# PicoUSBMotherboardV3_0.net
KiCad netlist of a schematic drawn in EasyEDA Pro
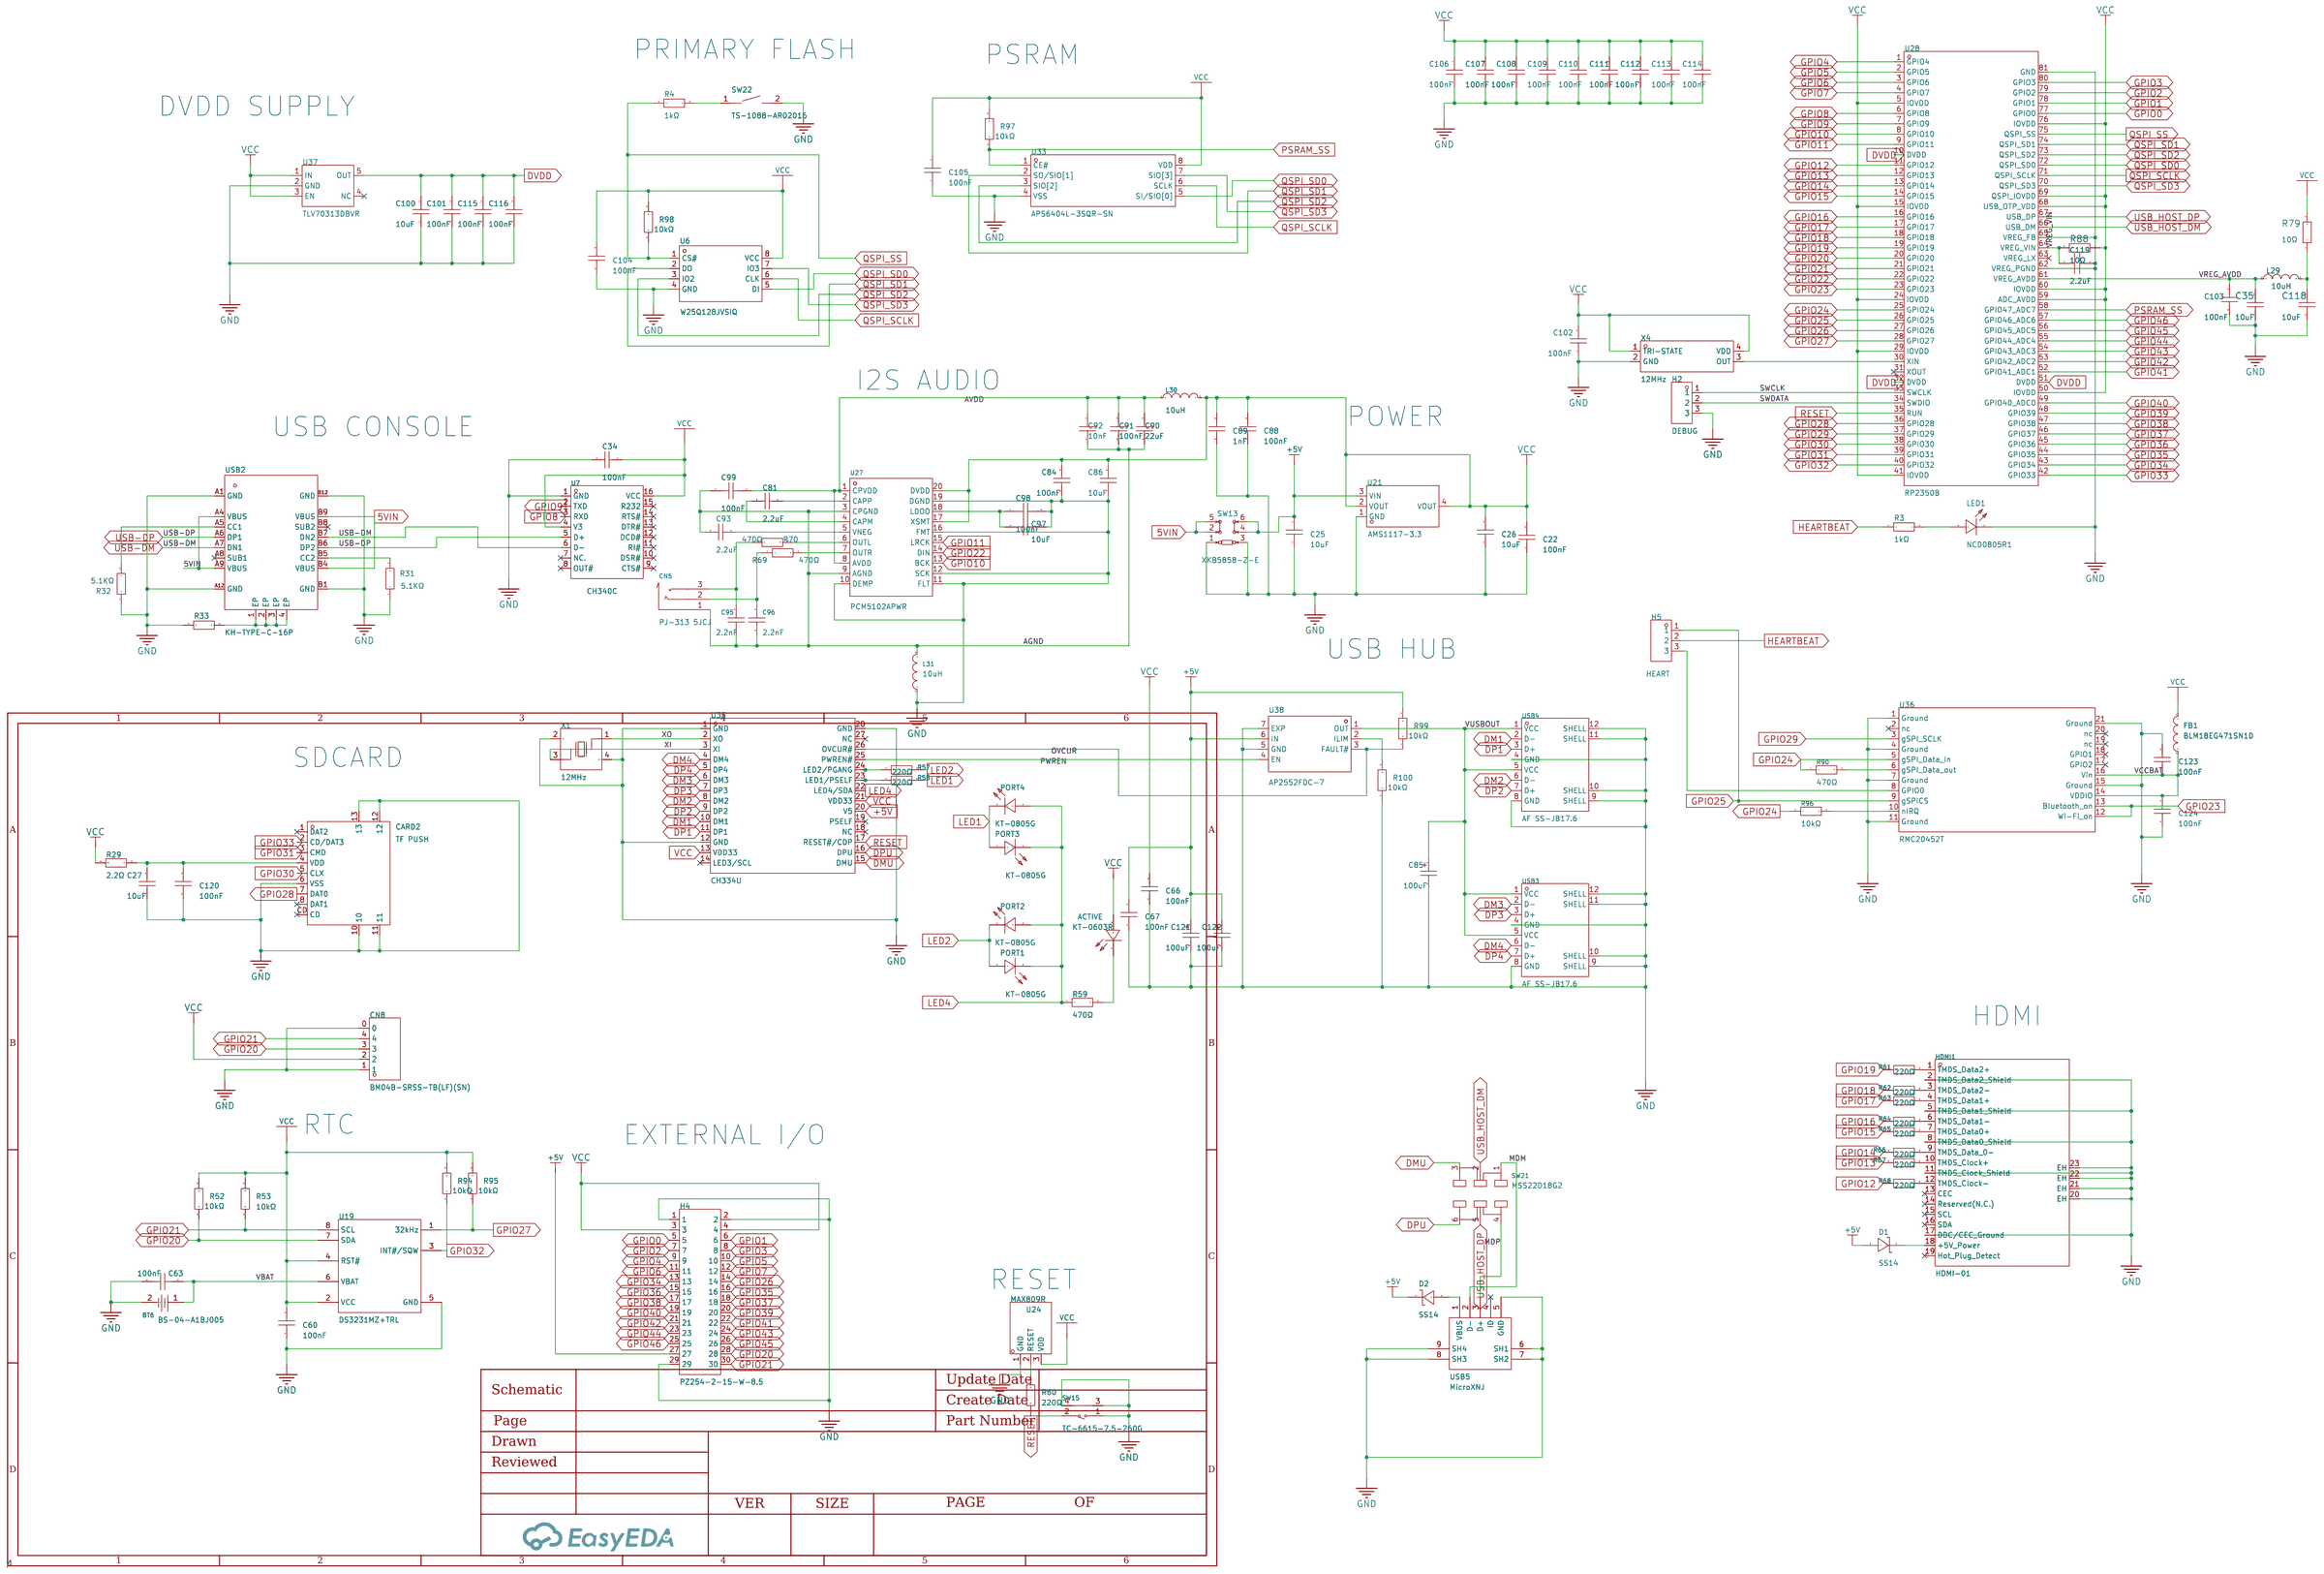
[diagram p0: schematic sheet]

(export (version "E")
  (design (tool "Eeschema 10.0.6"))
  (components
    (comp (ref "ACTIVE")
      (value "KT-0603R")
      (footprint "easyedapro:LED0603-RD")
      (fields (field (name "Manufacturer") "KENTO"))
      (libsource (lib "easyedapro") (part "KT-0603R"))
    )
    (comp (ref "BT6")
      (value "BS-04-A1BJ005")
      (footprint "easyedapro:BAT-TH_BS-04-A1BJ004")
      (fields (field (name "Manufacturer") "MYOUNG(美阳)"))
      (libsource (lib "easyedapro") (part "BS-04-A1BJ005"))
    )
    (comp (ref "C22")
      (value "100nF")
      (fields
        (field (name "Manufacturer Part") "CL05B104KO5NNNC")
        (field (name "Manufacturer") "SAMSUNG(三星)")
      )
      (libsource (lib "easyedapro") (part "cl10a225ko8nnnc"))
    )
    (comp (ref "C25")
      (value "10uF")
      (footprint "easyedapro:C1206")
      (fields
        (field (name "Manufacturer Part") "CL31A106KBHNNNE")
        (field (name "Manufacturer") "SAMSUNG(三星)")
      )
      (libsource (lib "easyedapro") (part "CL31A106KBHNNNE"))
    )
    (comp (ref "C26")
      (value "10uF")
      (footprint "easyedapro:C1206")
      (fields
        (field (name "Manufacturer Part") "CL31A106KBHNNNE")
        (field (name "Manufacturer") "SAMSUNG(三星)")
      )
      (libsource (lib "easyedapro") (part "CL31A106KBHNNNE"))
    )
    (comp (ref "C27")
      (value "10uF")
      (footprint "easyedapro:C1206")
      (fields
        (field (name "Manufacturer Part") "CL31A106KBHNNNE")
        (field (name "Manufacturer") "SAMSUNG(三星)")
      )
      (libsource (lib "easyedapro") (part "CL31A106KBHNNNE"))
    )
    (comp (ref "C34")
      (value "100nF")
      (fields
        (field (name "Manufacturer Part") "CL05B104KO5NNNC")
        (field (name "Manufacturer") "SAMSUNG(三星)")
      )
      (libsource (lib "easyedapro") (part "cl10a225ko8nnnc"))
    )
    (comp (ref "C35")
      (value "10uF")
      (footprint "easyedapro:C1206")
      (fields
        (field (name "Manufacturer Part") "CL31A106KBHNNNE")
        (field (name "Manufacturer") "SAMSUNG(三星)")
      )
      (libsource (lib "easyedapro") (part "CL31A106KBHNNNE"))
    )
    (comp (ref "C60")
      (value "100nF")
      (footprint "easyedapro:C0603")
      (fields
        (field (name "Manufacturer Part") "CL05B104KO5NNNC")
        (field (name "Manufacturer") "SAMSUNG(三星)")
      )
      (libsource (lib "easyedapro") (part "CL10A225KO8NNNC"))
    )
    (comp (ref "C63")
      (value "100nF")
      (footprint "easyedapro:C0402")
      (fields
        (field (name "Manufacturer Part") "CL05B104KB54PNC")
        (field (name "Manufacturer") "SAMSUNG(三星)")
      )
      (libsource (lib "easyedapro") (part "CL05B104KB54PNC"))
    )
    (comp (ref "C66")
      (value "100nF")
      (fields
        (field (name "Manufacturer Part") "CL05B104KO5NNNC")
        (field (name "Manufacturer") "SAMSUNG(三星)")
      )
      (libsource (lib "easyedapro") (part "cl10a225ko8nnnc"))
    )
    (comp (ref "C67")
      (value "100nF")
      (fields
        (field (name "Manufacturer Part") "CL05B104KO5NNNC")
        (field (name "Manufacturer") "SAMSUNG(三星)")
      )
      (libsource (lib "easyedapro") (part "cl10a225ko8nnnc"))
    )
    (comp (ref "C81")
      (value "2.2uF")
      (footprint "easyedapro:C0603")
      (fields
        (field (name "Manufacturer Part") "CL10A225KO8NNNC")
        (field (name "Manufacturer") "SAMSUNG(三星)")
      )
      (libsource (lib "easyedapro") (part "CL10A225KO8NNNC"))
    )
    (comp (ref "C84")
      (value "100nF")
      (fields
        (field (name "Manufacturer Part") "CL05B104KO5NNNC")
        (field (name "Manufacturer") "SAMSUNG(三星)")
      )
      (libsource (lib "easyedapro") (part "cl10a225ko8nnnc"))
    )
    (comp (ref "C85")
      (value "100uF")
      (footprint "easyedapro:CASE-B_3528")
      (fields (field (name "Manufacturer Part") "TAJB107K006RNJ") (field (name "Manufacturer") "Kyocera AVX"))
      (libsource (lib "easyedapro") (part "TAJB107K006RNJ"))
    )
    (comp (ref "C86")
      (value "10uF")
      (footprint "easyedapro:C1206")
      (fields
        (field (name "Manufacturer Part") "CL31A106KBHNNNE")
        (field (name "Manufacturer") "SAMSUNG(三星)")
      )
      (libsource (lib "easyedapro") (part "CL31A106KBHNNNE"))
    )
    (comp (ref "C88")
      (value "100nF")
      (fields
        (field (name "Manufacturer Part") "CL05B104KO5NNNC")
        (field (name "Manufacturer") "SAMSUNG(三星)")
      )
      (libsource (lib "easyedapro") (part "cl10a225ko8nnnc"))
    )
    (comp (ref "C89")
      (value "1nF")
      (footprint "easyedapro:C0805")
      (fields
        (field (name "Manufacturer Part") "CL21B102KBCNNNC")
        (field (name "Manufacturer") "SAMSUNG(三星)")
      )
      (libsource (lib "easyedapro") (part "CL21B102KBCNNNC"))
    )
    (comp (ref "C90")
      (value "22uF")
      (footprint "easyedapro:C1206")
      (fields
        (field (name "Manufacturer Part") "CL31A226KAHNNNE")
        (field (name "Manufacturer") "SAMSUNG(三星)")
      )
      (libsource (lib "easyedapro") (part "CL31A226KAHNNNE"))
    )
    (comp (ref "C91")
      (value "100nF")
      (fields
        (field (name "Manufacturer Part") "CL05B104KO5NNNC")
        (field (name "Manufacturer") "SAMSUNG(三星)")
      )
      (libsource (lib "easyedapro") (part "cl10a225ko8nnnc"))
    )
    (comp (ref "C92")
      (value "10nF")
      (footprint "easyedapro:C0805")
      (fields
        (field (name "Manufacturer Part") "CL21B103KBANNNC")
        (field (name "Manufacturer") "SAMSUNG(三星)")
      )
      (libsource (lib "easyedapro") (part "CL21B103KBANNNC"))
    )
    (comp (ref "C93")
      (value "2.2uF")
      (footprint "easyedapro:C0603")
      (fields
        (field (name "Manufacturer Part") "CL10A225KO8NNNC")
        (field (name "Manufacturer") "SAMSUNG(三星)")
      )
      (libsource (lib "easyedapro") (part "CL10A225KO8NNNC"))
    )
    (comp (ref "C95")
      (value "2.2nF")
      (footprint "easyedapro:C0805")
      (fields
        (field (name "Manufacturer Part") "CL21C222JBFNNNE")
        (field (name "Manufacturer") "SAMSUNG(三星)")
      )
      (libsource (lib "easyedapro") (part "CL21C222JBFNNNE"))
    )
    (comp (ref "C96")
      (value "2.2nF")
      (footprint "easyedapro:C0805")
      (fields
        (field (name "Manufacturer Part") "CL21C222JBFNNNE")
        (field (name "Manufacturer") "SAMSUNG(三星)")
      )
      (libsource (lib "easyedapro") (part "CL21C222JBFNNNE"))
    )
    (comp (ref "C97")
      (value "10uF")
      (footprint "easyedapro:C0805")
      (fields
        (field (name "Manufacturer Part") "CL21A106KAYNNNE")
        (field (name "Manufacturer") "SAMSUNG(三星)")
      )
      (libsource (lib "easyedapro") (part "CL21A106KAYNNNE"))
    )
    (comp (ref "C98")
      (value "100nF")
      (footprint "easyedapro:C0805")
      (fields
        (field (name "Manufacturer Part") "CC0805KRX7R9BB104")
        (field (name "Manufacturer") "YAGEO(国巨)")
      )
      (libsource (lib "easyedapro") (part "CC0805KRX7R9BB104"))
    )
    (comp (ref "C99")
      (value "100nF")
      (footprint "easyedapro:C0805")
      (fields
        (field (name "Manufacturer Part") "CC0805KRX7R9BB104")
        (field (name "Manufacturer") "YAGEO(国巨)")
      )
      (libsource (lib "easyedapro") (part "CC0805KRX7R9BB104"))
    )
    (comp (ref "C100")
      (value "10uF")
      (footprint "easyedapro:C1206")
      (fields
        (field (name "Manufacturer Part") "CL31A106KBHNNNE")
        (field (name "Manufacturer") "SAMSUNG(三星)")
      )
      (libsource (lib "easyedapro") (part "CL31A106KBHNNNE"))
    )
    (comp (ref "C101")
      (value "100nF")
      (fields
        (field (name "Manufacturer Part") "CL05B104KO5NNNC")
        (field (name "Manufacturer") "SAMSUNG(三星)")
      )
      (libsource (lib "easyedapro") (part "cl10a225ko8nnnc"))
    )
    (comp (ref "C102")
      (value "100nF")
      (fields
        (field (name "Manufacturer Part") "CL05B104KO5NNNC")
        (field (name "Manufacturer") "SAMSUNG(三星)")
      )
      (libsource (lib "easyedapro") (part "cl10a225ko8nnnc"))
    )
    (comp (ref "C103")
      (value "100nF")
      (fields
        (field (name "Manufacturer Part") "CL05B104KO5NNNC")
        (field (name "Manufacturer") "SAMSUNG(三星)")
      )
      (libsource (lib "easyedapro") (part "cl10a225ko8nnnc"))
    )
    (comp (ref "C104")
      (value "100nF")
      (footprint "easyedapro:C0805")
      (fields
        (field (name "Manufacturer Part") "CL21B104KCFNNNE")
        (field (name "Manufacturer") "SAMSUNG(三星)")
      )
      (libsource (lib "easyedapro") (part "CL21B104KCFNNNE"))
    )
    (comp (ref "C105")
      (value "100nF")
      (fields
        (field (name "Manufacturer Part") "CL05B104KO5NNNC")
        (field (name "Manufacturer") "SAMSUNG(三星)")
      )
      (libsource (lib "easyedapro") (part "cl10a225ko8nnnc"))
    )
    (comp (ref "C106")
      (value "100nF")
      (fields
        (field (name "Manufacturer Part") "CL05B104KO5NNNC")
        (field (name "Manufacturer") "SAMSUNG(三星)")
      )
      (libsource (lib "easyedapro") (part "cl10a225ko8nnnc"))
    )
    (comp (ref "C107")
      (value "100nF")
      (fields
        (field (name "Manufacturer Part") "CL05B104KO5NNNC")
        (field (name "Manufacturer") "SAMSUNG(三星)")
      )
      (libsource (lib "easyedapro") (part "cl10a225ko8nnnc"))
    )
    (comp (ref "C108")
      (value "100nF")
      (fields
        (field (name "Manufacturer Part") "CL05B104KO5NNNC")
        (field (name "Manufacturer") "SAMSUNG(三星)")
      )
      (libsource (lib "easyedapro") (part "cl10a225ko8nnnc"))
    )
    (comp (ref "C109")
      (value "100nF")
      (fields
        (field (name "Manufacturer Part") "CL05B104KO5NNNC")
        (field (name "Manufacturer") "SAMSUNG(三星)")
      )
      (libsource (lib "easyedapro") (part "cl10a225ko8nnnc"))
    )
    (comp (ref "C110")
      (value "100nF")
      (fields
        (field (name "Manufacturer Part") "CL05B104KO5NNNC")
        (field (name "Manufacturer") "SAMSUNG(三星)")
      )
      (libsource (lib "easyedapro") (part "cl10a225ko8nnnc"))
    )
    (comp (ref "C111")
      (value "100nF")
      (fields
        (field (name "Manufacturer Part") "CL05B104KO5NNNC")
        (field (name "Manufacturer") "SAMSUNG(三星)")
      )
      (libsource (lib "easyedapro") (part "cl10a225ko8nnnc"))
    )
    (comp (ref "C112")
      (value "100nF")
      (fields
        (field (name "Manufacturer Part") "CL05B104KO5NNNC")
        (field (name "Manufacturer") "SAMSUNG(三星)")
      )
      (libsource (lib "easyedapro") (part "cl10a225ko8nnnc"))
    )
    (comp (ref "C113")
      (value "100nF")
      (fields
        (field (name "Manufacturer Part") "CL05B104KO5NNNC")
        (field (name "Manufacturer") "SAMSUNG(三星)")
      )
      (libsource (lib "easyedapro") (part "cl10a225ko8nnnc"))
    )
    (comp (ref "C114")
      (value "100nF")
      (fields
        (field (name "Manufacturer Part") "CL05B104KO5NNNC")
        (field (name "Manufacturer") "SAMSUNG(三星)")
      )
      (libsource (lib "easyedapro") (part "cl10a225ko8nnnc"))
    )
    (comp (ref "C115")
      (value "100nF")
      (fields
        (field (name "Manufacturer Part") "CL05B104KO5NNNC")
        (field (name "Manufacturer") "SAMSUNG(三星)")
      )
      (libsource (lib "easyedapro") (part "cl10a225ko8nnnc"))
    )
    (comp (ref "C116")
      (value "100nF")
      (fields
        (field (name "Manufacturer Part") "CL05B104KO5NNNC")
        (field (name "Manufacturer") "SAMSUNG(三星)")
      )
      (libsource (lib "easyedapro") (part "cl10a225ko8nnnc"))
    )
    (comp (ref "C118")
      (value "10uF")
      (footprint "easyedapro:C1206")
      (fields
        (field (name "Manufacturer Part") "CL31A106KBHNNNE")
        (field (name "Manufacturer") "SAMSUNG(三星)")
      )
      (libsource (lib "easyedapro") (part "CL31A106KBHNNNE"))
    )
    (comp (ref "C119")
      (value "2.2uF")
      (footprint "easyedapro:C0402")
      (fields
        (field (name "Manufacturer Part") "CL05A225MQ5NSNC")
        (field (name "Manufacturer") "SAMSUNG(三星)")
      )
      (libsource (lib "easyedapro") (part "CL05A225MQ5NSNC"))
    )
    (comp (ref "C120")
      (value "100nF")
      (footprint "easyedapro:C0805")
      (fields
        (field (name "Manufacturer Part") "CL21B104KCFNNNE")
        (field (name "Manufacturer") "SAMSUNG(三星)")
      )
      (libsource (lib "easyedapro") (part "CL21B104KCFNNNE"))
    )
    (comp (ref "C121")
      (value "100uF")
      (footprint "easyedapro:CASE-B_3528")
      (fields (field (name "Manufacturer Part") "TAJB107K006RNJ") (field (name "Manufacturer") "Kyocera AVX"))
      (libsource (lib "easyedapro") (part "TAJB107K006RNJ"))
    )
    (comp (ref "C122")
      (value "100uF")
      (footprint "easyedapro:CASE-B_3528")
      (fields (field (name "Manufacturer Part") "TAJB107K006RNJ") (field (name "Manufacturer") "Kyocera AVX"))
      (libsource (lib "easyedapro") (part "TAJB107K006RNJ"))
    )
    (comp (ref "C123")
      (value "100nF")
      (fields
        (field (name "Manufacturer Part") "CL05B104KO5NNNC")
        (field (name "Manufacturer") "SAMSUNG(三星)")
      )
      (libsource (lib "easyedapro") (part "cl10a225ko8nnnc"))
    )
    (comp (ref "C124")
      (value "100nF")
      (fields
        (field (name "Manufacturer Part") "CL05B104KO5NNNC")
        (field (name "Manufacturer") "SAMSUNG(三星)")
      )
      (libsource (lib "easyedapro") (part "cl10a225ko8nnnc"))
    )
    (comp (ref "CARD2")
      (value "TF PUSH")
      (footprint "easyedapro:TF-SMD_TF-PUSH")
      (fields (field (name "Manufacturer") "SHOU HAN(首韩)"))
      (libsource (lib "easyedapro") (part "TF PUSH"))
    )
    (comp (ref "CN5")
      (value "PJ-313 5JCJ")
      (footprint "easyedapro:AUDIO-TH_PJ-313_5JCJ")
      (fields (field (name "Manufacturer") "SHOU HAN(首韩)"))
      (libsource (lib "easyedapro") (part "PJ-313 5JCJ"))
    )
    (comp (ref "CN8")
      (value "BM04B-SRSS-TB(LF)(SN)")
      (footprint "easyedapro:CONN-SMD_BM04B-SRSS-TB")
      (fields (field (name "Manufacturer") "JST"))
      (libsource (lib "easyedapro") (part "BM04B-SRSS-TB(LF)(SN)"))
    )
    (comp (ref "D1")
      (value "SS14")
      (footprint "easyedapro:SMA_L4.2-W2.6-LS5.3-RD")
      (fields (field (name "Manufacturer") "MDD(辰达半导体)"))
      (libsource (lib "easyedapro") (part "SS14"))
    )
    (comp (ref "D2")
      (value "SS14")
      (footprint "easyedapro:SMA_L4.2-W2.6-LS5.3-RD")
      (fields (field (name "Manufacturer") "MDD(辰达半导体)"))
      (libsource (lib "easyedapro") (part "SS14"))
    )
    (comp (ref "FB1")
      (value "BLM18EG471SN1D")
      (footprint "easyedapro:L0603")
      (fields (field (name "Manufacturer") "muRata(村田)"))
      (libsource (lib "easyedapro") (part "BLM18EG471SN1D"))
    )
    (comp (ref "H2")
      (value "DEBUG")
      (footprint "easyedapro:HDR-TH_3P-P2.54-V-M")
      (fields (field (name "Manufacturer Part") "PZ254V-11-03P") (field (name "Manufacturer") "XFCN(兴飞)"))
      (libsource (lib "easyedapro") (part "PZ254V-11-03P_C2937625"))
    )
    (comp (ref "H4")
      (value "PZ254-2-15-W-8.5")
      (footprint "easyedapro:HDR-TH_30P-P2.54-H-M-R2-C15-S2.54-N")
      (fields (field (name "Manufacturer") "HCTL(华灿天禄)"))
      (libsource (lib "easyedapro") (part "PZ254-2-15-W-8.5"))
    )
    (comp (ref "H5")
      (value "HEART")
      (footprint "easyedapro:HDR-TH_3P-P2.54-V-M")
      (fields (field (name "Manufacturer Part") "PZ254V-11-03P") (field (name "Manufacturer") "XFCN(兴飞)"))
      (libsource (lib "easyedapro") (part "PZ254V-11-03P_C2937625"))
    )
    (comp (ref "HDMI1")
      (value "HDMI-01")
      (footprint "easyedapro:USB-SMD_HDMI-01")
      (fields (field (name "Manufacturer") "HCTL(华灿天禄)"))
      (libsource (lib "easyedapro") (part "HDMI-01"))
    )
    (comp (ref "L29")
      (value "10uH")
      (fields
        (field (name "Manufacturer Part") "SDFL2012S100KTF")
        (field (name "Manufacturer") "Sunlord(顺络)")
      )
      (libsource (lib "easyedapro") (part "SDFL2012S100KTF"))
    )
    (comp (ref "L30")
      (value "10uH")
      (footprint "easyedapro:L0805")
      (fields (field (name "Manufacturer Part") "MLZ2012M100HT000") (field (name "Manufacturer") "TDK"))
      (libsource (lib "easyedapro") (part "MLZ2012M100HT000"))
    )
    (comp (ref "L31")
      (value "10uH")
      (footprint "easyedapro:L0805")
      (fields (field (name "Manufacturer Part") "MLZ2012M100HT000") (field (name "Manufacturer") "TDK"))
      (libsource (lib "easyedapro") (part "MLZ2012M100HT000"))
    )
    (comp (ref "LED1")
      (value "NCD0805R1")
      (footprint "easyedapro:LED0805-RD")
      (description "Emitted Color:红灯")
      (fields (field (name "Manufacturer") "国星光电"))
      (libsource (lib "easyedapro") (part "FC-2012HRK-620D"))
    )
    (comp (ref "PORT1")
      (value "KT-0805G")
      (footprint "easyedapro:LED0805-R-RD")
      (fields (field (name "Manufacturer") "KENTO"))
      (libsource (lib "easyedapro") (part "0805G (Green)"))
    )
    (comp (ref "PORT2")
      (value "KT-0805G")
      (footprint "easyedapro:LED0805-R-RD")
      (fields (field (name "Manufacturer") "KENTO"))
      (libsource (lib "easyedapro") (part "0805G (Green)"))
    )
    (comp (ref "PORT3")
      (value "KT-0805G")
      (footprint "easyedapro:LED0805-R-RD")
      (fields (field (name "Manufacturer") "KENTO"))
      (libsource (lib "easyedapro") (part "0805G (Green)"))
    )
    (comp (ref "PORT4")
      (value "KT-0805G")
      (footprint "easyedapro:LED0805-R-RD")
      (fields (field (name "Manufacturer") "KENTO"))
      (libsource (lib "easyedapro") (part "0805G (Green)"))
    )
    (comp (ref "R3")
      (value "1kΩ")
      (footprint "easyedapro:R0603")
      (fields
        (field (name "Manufacturer Part") "0603WAF1001T5E")
        (field (name "Manufacturer") "UNI-ROYAL(厚声)")
      )
      (libsource (lib "easyedapro") (part "0603WAF1001T5E"))
    )
    (comp (ref "R4")
      (value "1kΩ")
      (footprint "easyedapro:R0603")
      (fields
        (field (name "Manufacturer Part") "0603WAF1001T5E")
        (field (name "Manufacturer") "UNI-ROYAL(厚声)")
      )
      (libsource (lib "easyedapro") (part "0603WAF1001T5E"))
    )
    (comp (ref "R29")
      (value "2.2Ω")
      (footprint "easyedapro:R0805")
      (fields (field (name "Manufacturer") "UNI-ROYAL(厚声)"))
      (libsource (lib "easyedapro") (part "0805W8F220KT5E"))
    )
    (comp (ref "R31")
      (value "5.1kΩ")
      (fields
        (field (name "Manufacturer Part") "5.1KΩ")
        (field (name "Manufacturer") "UNI-ROYAL(厚声)")
        (field (name "Tolerance") "±1%")
      )
      (libsource (lib "easyedapro") (part "0603waf5101t5e"))
    )
    (comp (ref "R32")
      (value "5.1kΩ")
      (fields
        (field (name "Manufacturer Part") "5.1KΩ")
        (field (name "Manufacturer") "UNI-ROYAL(厚声)")
        (field (name "Tolerance") "±1%")
      )
      (libsource (lib "easyedapro") (part "0603waf5101t5e"))
    )
    (comp (ref "R33")
      (value "1MΩ")
      (fields
        (field (name "Manufacturer Part") "0402WGF1004TCE")
        (field (name "Manufacturer") "UNI-ROYAL(厚声)")
      )
      (libsource (lib "easyedapro") (part "0603waf1004t5e"))
    )
    (comp (ref "R52")
      (value "10kΩ")
      (footprint "easyedapro:R0805")
      (fields
        (field (name "Manufacturer Part") "0805W8F1002T5E")
        (field (name "Manufacturer") "UNI-ROYAL(厚声)")
      )
      (libsource (lib "easyedapro") (part "0805W8F1002T5E"))
    )
    (comp (ref "R53")
      (value "10kΩ")
      (footprint "easyedapro:R0805")
      (fields
        (field (name "Manufacturer Part") "0805W8F1002T5E")
        (field (name "Manufacturer") "UNI-ROYAL(厚声)")
      )
      (libsource (lib "easyedapro") (part "0805W8F1002T5E"))
    )
    (comp (ref "R57")
      (value "220Ω")
      (footprint "easyedapro:R0805")
      (fields
        (field (name "Manufacturer Part") "0805W8F2200T5E")
        (field (name "Manufacturer") "UNI-ROYAL(厚声)")
      )
      (libsource (lib "easyedapro") (part "0805W8F2200T5E"))
    )
    (comp (ref "R58")
      (value "220Ω")
      (footprint "easyedapro:R0805")
      (fields
        (field (name "Manufacturer Part") "0805W8F2200T5E")
        (field (name "Manufacturer") "UNI-ROYAL(厚声)")
      )
      (libsource (lib "easyedapro") (part "0805W8F2200T5E"))
    )
    (comp (ref "R59")
      (value "470Ω")
      (footprint "easyedapro:R0603")
      (fields
        (field (name "Manufacturer Part") "0603WAF4700T5E")
        (field (name "Manufacturer") "UNI-ROYAL(厚声)")
      )
      (libsource (lib "easyedapro") (part "0603WAF4700T5E"))
    )
    (comp (ref "R60")
      (value "220Ω")
      (footprint "easyedapro:R0603")
      (fields
        (field (name "Manufacturer Part") "0603WAF2200T5E")
        (field (name "Manufacturer") "UNI-ROYAL(厚声)")
      )
      (libsource (lib "easyedapro") (part "0603WAF2200T5E"))
    )
    (comp (ref "R61")
      (value "220Ω")
      (footprint "easyedapro:R0603")
      (fields
        (field (name "Manufacturer Part") "0603WAF2200T5E")
        (field (name "Manufacturer") "UNI-ROYAL(厚声)")
      )
      (libsource (lib "easyedapro") (part "0603WAF2200T5E"))
    )
    (comp (ref "R62")
      (value "220Ω")
      (footprint "easyedapro:R0603")
      (fields
        (field (name "Manufacturer Part") "0603WAF2200T5E")
        (field (name "Manufacturer") "UNI-ROYAL(厚声)")
      )
      (libsource (lib "easyedapro") (part "0603WAF2200T5E"))
    )
    (comp (ref "R63")
      (value "220Ω")
      (footprint "easyedapro:R0603")
      (fields
        (field (name "Manufacturer Part") "0603WAF2200T5E")
        (field (name "Manufacturer") "UNI-ROYAL(厚声)")
      )
      (libsource (lib "easyedapro") (part "0603WAF2200T5E"))
    )
    (comp (ref "R64")
      (value "220Ω")
      (footprint "easyedapro:R0603")
      (fields
        (field (name "Manufacturer Part") "0603WAF2200T5E")
        (field (name "Manufacturer") "UNI-ROYAL(厚声)")
      )
      (libsource (lib "easyedapro") (part "0603WAF2200T5E"))
    )
    (comp (ref "R65")
      (value "220Ω")
      (footprint "easyedapro:R0603")
      (fields
        (field (name "Manufacturer Part") "0603WAF2200T5E")
        (field (name "Manufacturer") "UNI-ROYAL(厚声)")
      )
      (libsource (lib "easyedapro") (part "0603WAF2200T5E"))
    )
    (comp (ref "R66")
      (value "220Ω")
      (footprint "easyedapro:R0603")
      (fields
        (field (name "Manufacturer Part") "0603WAF2200T5E")
        (field (name "Manufacturer") "UNI-ROYAL(厚声)")
      )
      (libsource (lib "easyedapro") (part "0603WAF2200T5E"))
    )
    (comp (ref "R67")
      (value "220Ω")
      (footprint "easyedapro:R0603")
      (fields
        (field (name "Manufacturer Part") "0603WAF2200T5E")
        (field (name "Manufacturer") "UNI-ROYAL(厚声)")
      )
      (libsource (lib "easyedapro") (part "0603WAF2200T5E"))
    )
    (comp (ref "R68")
      (value "220Ω")
      (footprint "easyedapro:R0603")
      (fields
        (field (name "Manufacturer Part") "0603WAF2200T5E")
        (field (name "Manufacturer") "UNI-ROYAL(厚声)")
      )
      (libsource (lib "easyedapro") (part "0603WAF2200T5E"))
    )
    (comp (ref "R69")
      (value "470Ω")
      (footprint "easyedapro:R0603")
      (fields
        (field (name "Manufacturer Part") "0603WAF4700T5E")
        (field (name "Manufacturer") "UNI-ROYAL(厚声)")
      )
      (libsource (lib "easyedapro") (part "0603WAF4700T5E"))
    )
    (comp (ref "R70")
      (value "470Ω")
      (footprint "easyedapro:R0603")
      (fields
        (field (name "Manufacturer Part") "0603WAF4700T5E")
        (field (name "Manufacturer") "UNI-ROYAL(厚声)")
      )
      (libsource (lib "easyedapro") (part "0603WAF4700T5E"))
    )
    (comp (ref "R79")
      (value "10Ω")
      (footprint "easyedapro:R0805_NEW")
      (fields
        (field (name "Manufacturer Part") "0805W8F100JT5E")
        (field (name "Manufacturer") "UNI-ROYAL(厚声)")
      )
      (libsource (lib "easyedapro") (part "0805W8F100JT5E"))
    )
    (comp (ref "R88")
      (value "10Ω")
      (footprint "easyedapro:R0805_NEW")
      (fields
        (field (name "Manufacturer Part") "0805W8F100JT5E")
        (field (name "Manufacturer") "UNI-ROYAL(厚声)")
      )
      (libsource (lib "easyedapro") (part "0805W8F100JT5E"))
    )
    (comp (ref "R90")
      (value "470Ω")
      (footprint "easyedapro:R0402")
      (fields
        (field (name "Manufacturer Part") "0402WGF4700TCE")
        (field (name "Manufacturer") "UNI-ROYAL(厚声)")
      )
      (libsource (lib "easyedapro") (part "0402WGF4700TCE"))
    )
    (comp (ref "R94")
      (value "10kΩ")
      (footprint "easyedapro:R0805")
      (fields
        (field (name "Manufacturer Part") "0805W8F1002T5E")
        (field (name "Manufacturer") "UNI-ROYAL(厚声)")
      )
      (libsource (lib "easyedapro") (part "0805W8F1002T5E"))
    )
    (comp (ref "R95")
      (value "10kΩ")
      (footprint "easyedapro:R0805")
      (fields
        (field (name "Manufacturer Part") "0805W8F1002T5E")
        (field (name "Manufacturer") "UNI-ROYAL(厚声)")
      )
      (libsource (lib "easyedapro") (part "0805W8F1002T5E"))
    )
    (comp (ref "R96")
      (value "10kΩ")
      (footprint "easyedapro:R0603")
      (fields
        (field (name "Manufacturer Part") "0603WAF1002T5E")
        (field (name "Manufacturer") "UNI-ROYAL(厚声)")
      )
      (libsource (lib "easyedapro") (part "0603WAF1002T5E"))
    )
    (comp (ref "R97")
      (value "10kΩ")
      (footprint "easyedapro:R0805")
      (fields
        (field (name "Manufacturer Part") "0805W8F1002T5E")
        (field (name "Manufacturer") "UNI-ROYAL(厚声)")
      )
      (libsource (lib "easyedapro") (part "0805W8F1002T5E"))
    )
    (comp (ref "R98")
      (value "10kΩ")
      (footprint "easyedapro:R0805")
      (fields
        (field (name "Manufacturer Part") "0805W8F1002T5E")
        (field (name "Manufacturer") "UNI-ROYAL(厚声)")
      )
      (libsource (lib "easyedapro") (part "0805W8F1002T5E"))
    )
    (comp (ref "R99")
      (value "10kΩ")
      (footprint "easyedapro:R0805")
      (fields
        (field (name "Manufacturer Part") "0805W8F1002T5E")
        (field (name "Manufacturer") "UNI-ROYAL(厚声)")
      )
      (libsource (lib "easyedapro") (part "0805W8F1002T5E"))
    )
    (comp (ref "R100")
      (value "10kΩ")
      (footprint "easyedapro:R0805")
      (fields
        (field (name "Manufacturer Part") "0805W8F1002T5E")
        (field (name "Manufacturer") "UNI-ROYAL(厚声)")
      )
      (libsource (lib "easyedapro") (part "0805W8F1002T5E"))
    )
    (comp (ref "SW13")
      (value "XKB5858-Z-E")
      (footprint "easyedapro:SW-TH_XKB5858-Z-E")
      (fields (field (name "Manufacturer") "XKB Connectivity(中国星坤)"))
      (libsource (lib "easyedapro") (part "XKB5858-Z-E"))
    )
    (comp (ref "SW15")
      (value "TC-6615-7.5-260G")
      (footprint "easyedapro:SW-TH_4P-L7.5-W7.5-P4.50")
      (fields (field (name "Manufacturer") "HCTL(华灿天禄)"))
      (libsource (lib "easyedapro") (part "TC-6615-7.5-260G"))
    )
    (comp (ref "SW21")
      (value "MSS22D18G2")
      (footprint "easyedapro:SW-TH_MSS22D18GX")
      (fields (field (name "Manufacturer") "SHOU HAN(首韩)"))
      (libsource (lib "easyedapro") (part "MSS22D18G2"))
    )
    (comp (ref "SW22")
      (value "TS-1088-AR02016")
      (footprint "easyedapro:SW-SMD_L3.9-W3.0-P4.45")
      (fields (field (name "Manufacturer") "XUNPU(讯普)"))
      (libsource (lib "easyedapro") (part "TS-1088-AR02016"))
    )
    (comp (ref "U6")
      (value "W25Q128JVSIQ")
      (footprint "easyedapro:SOIC-8_L5.3-W5.3-P1.27-LS8.0-BL")
      (fields (field (name "Manufacturer") "WINBOND(华邦)"))
      (libsource (lib "easyedapro") (part "W25Q128JVSIQTR"))
    )
    (comp (ref "U7")
      (value "CH340C")
      (footprint "easyedapro:SOP-16_L10.0-W3.9-P1.27-LS6.0-BL")
      (fields (field (name "Manufacturer") "WCH(南京沁恒)"))
      (libsource (lib "easyedapro") (part "CH340C"))
    )
    (comp (ref "U19")
      (value "DS3231MZ+TRL")
      (footprint "easyedapro:SOIC-8_L4.9-W3.9-P1.27-LS6.0-BL")
      (fields (field (name "Manufacturer") "ADI(亚德诺)/MAXIM(美信)"))
      (libsource (lib "easyedapro") (part "DS3231MZ+"))
    )
    (comp (ref "U21")
      (value "AMS1117-3.3")
      (footprint "easyedapro:SOT-223-3_L6.5-W3.4-P2.30-LS7.0-BR")
      (fields (field (name "Manufacturer") "AMS"))
      (libsource (lib "easyedapro") (part "AMS1117-3.3"))
    )
    (comp (ref "U24")
      (value "MAX809R")
      (footprint "easyedapro:SOT-23-3_L2.9-W1.3-P1.90-LS2.4-BR")
      (fields (field (name "Manufacturer") "UMW(友台半导体)"))
      (libsource (lib "easyedapro") (part "MAX809R"))
    )
    (comp (ref "U27")
      (value "PCM5102APWR")
      (footprint "easyedapro:TSSOP-20_L6.5-W4.4-P0.65-LS6.4-BL")
      (fields (field (name "Manufacturer") "TI(德州仪器)"))
      (libsource (lib "easyedapro") (part "PCM5102APWR"))
    )
    (comp (ref "U28")
      (value "RP2350B")
      (footprint "easyedapro:QFN-80_L10.0-W10.0-P0.40-TL-EP3.4")
      (fields (field (name "Manufacturer") "Raspberry Pi(树莓派)"))
      (libsource (lib "easyedapro") (part "RP2350B_C42415655"))
    )
    (comp (ref "U33")
      (value "APS6404L-3SQR-SN")
      (footprint "easyedapro:SOIC-8_L4.9-W3.9-P1.27-LS6.0-BL")
      (fields (field (name "Manufacturer") "Apmemory"))
      (libsource (lib "easyedapro") (part "APS6404L-3SQR-SN_C5333729"))
    )
    (comp (ref "U35")
      (value "CH334U")
      (footprint "easyedapro:QSOP-28_L9.9-W3.9-P0.64-LS6.0-BL")
      (fields (field (name "Manufacturer") "WCH(南京沁恒)"))
      (libsource (lib "easyedapro") (part "CH334U"))
    )
    (comp (ref "U36")
      (value "RMC20452T")
      (footprint "easyedapro:WIRELM-SMD_RMC20452T")
      (fields (field (name "Manufacturer") "Raspberry Pi(树莓派)"))
      (libsource (lib "easyedapro") (part "RMC20452T_C49451547"))
    )
    (comp (ref "U37")
      (value "TLV70313DBVR")
      (footprint "easyedapro:SOT-23-5_L3.0-W1.5-P0.95-LS2.8-BL")
      (fields (field (name "Manufacturer") "TI(德州仪器)"))
      (libsource (lib "easyedapro") (part "TLV70313DBVR"))
    )
    (comp (ref "U38")
      (value "AP2552FDC-7")
      (footprint "easyedapro:WDFN-6_L2.0-W2.0-P0.65-BL-EP-1")
      (fields (field (name "Manufacturer") "DIODES(美台)"))
      (libsource (lib "easyedapro") (part "AP2552FDC-7"))
    )
    (comp (ref "USB2")
      (value "KH-TYPE-C-16P")
      (footprint "easyedapro:USB-C-SMD_KH-TYPE-C-16P")
      (fields (field (name "Manufacturer") "kinghelm(金航标)"))
      (libsource (lib "easyedapro") (part "KH-TYPE-C-16P"))
    )
    (comp (ref "USB3")
      (value "AF SS-JB17.6")
      (footprint "easyedapro:USB-A-TH_AF-SS-JB17.6")
      (fields (field (name "Manufacturer") "SHOU HAN(首韩)"))
      (libsource (lib "easyedapro") (part "AF SS-JB17.6"))
    )
    (comp (ref "USB4")
      (value "AF SS-JB17.6")
      (footprint "easyedapro:USB-A-TH_AF-SS-JB17.6")
      (fields (field (name "Manufacturer") "SHOU HAN(首韩)"))
      (libsource (lib "easyedapro") (part "AF SS-JB17.6"))
    )
    (comp (ref "USB5")
      (value "MicroXNJ")
      (footprint "easyedapro:MICRO-USB-SMD_MICROXNJ")
      (fields (field (name "Manufacturer") "SHOU HAN(首韩)"))
      (libsource (lib "easyedapro") (part "MICROXNJ"))
    )
    (comp (ref "X1")
      (value "12MHz")
      (footprint "easyedapro:OSC-SMD_4P-L3.2-W2.5-BL")
      (fields (field (name "Manufacturer Part") "X322512MSB4SI") (field (name "Manufacturer") "YXC(扬兴晶振)"))
      (libsource (lib "easyedapro") (part "X322512MSB4SI"))
    )
    (comp (ref "X4")
      (value "12MHz")
      (footprint "easyedapro:OSC-SMD_4P-L3.2-W2.5-BL")
      (fields (field (name "Manufacturer Part") "XOS32012000LT00351005") (field (name "Manufacturer") "同晶"))
      (libsource (lib "easyedapro") (part "XOS32012000LT00351005"))
    )
  )
  (nets
    (net (code "1") (name "+5V") (class "Default")
      (node (ref "C121") (pin "1") (pinfunction "1_1") (pintype "input"))
      (node (ref "C122") (pin "1") (pinfunction "1_1") (pintype "input"))
      (node (ref "C25") (pin "2") (pinfunction "2_2") (pintype "input"))
      (node (ref "C67") (pin "2") (pinfunction "2_2") (pintype "input"))
      (node (ref "D1") (pin "2") (pinfunction "A_2") (pintype "unspecified"))
      (node (ref "D2") (pin "1") (pinfunction "K_1") (pintype "unspecified"))
      (node (ref "H4") (pin "27") (pinfunction "27_27") (pintype "unspecified"))
      (node (ref "R99") (pin "2") (pinfunction "2_2") (pintype "input"))
      (node (ref "SW13") (pin "4") (pinfunction "4_4") (pintype "input"))
      (node (ref "SW13") (pin "6") (pinfunction "6_6") (pintype "input"))
      (node (ref "U21") (pin "3") (pinfunction "VIN_3") (pintype "input"))
      (node (ref "U35") (pin "20") (pinfunction "V5_20") (pintype "unspecified"))
      (node (ref "U38") (pin "6") (pinfunction "IN_6") (pintype "unspecified"))
    )
    (net (code "2") (name "/AGND") (class "Default")
      (node (ref "C90") (pin "1") (pinfunction "1_1") (pintype "input"))
      (node (ref "C91") (pin "1") (pinfunction "1_1") (pintype "input"))
      (node (ref "C92") (pin "1") (pinfunction "1_1") (pintype "input"))
      (node (ref "C93") (pin "2") (pinfunction "2_2") (pintype "input"))
      (node (ref "C95") (pin "1") (pinfunction "1_1") (pintype "input"))
      (node (ref "C96") (pin "1") (pinfunction "1_1") (pintype "input"))
      (node (ref "C99") (pin "1") (pinfunction "1_1") (pintype "unspecified"))
      (node (ref "CN5") (pin "1") (pinfunction "1_1") (pintype "input"))
      (node (ref "L31") (pin "2") (pinfunction "2_2") (pintype "input"))
      (node (ref "U27") (pin "3") (pinfunction "CPGND_3") (pintype "input"))
      (node (ref "U27") (pin "9") (pinfunction "AGND_9") (pintype "input"))
    )
    (net (code "3") (name "/AVDD") (class "Default")
      (node (ref "C90") (pin "2") (pinfunction "2_2") (pintype "input"))
      (node (ref "C91") (pin "2") (pinfunction "2_2") (pintype "input"))
      (node (ref "C92") (pin "2") (pinfunction "2_2") (pintype "input"))
      (node (ref "C99") (pin "2") (pinfunction "2_2") (pintype "unspecified"))
      (node (ref "L30") (pin "1") (pinfunction "1_1") (pintype "input"))
      (node (ref "U27") (pin "1") (pinfunction "CPVDD_1") (pintype "input"))
      (node (ref "U27") (pin "8") (pinfunction "AVDD_8") (pintype "input"))
    )
    (net (code "4") (name "/MDM") (class "Default")
      (node (ref "SW21") (pin "1") (pinfunction "1_1") (pintype "input"))
      (node (ref "USB5") (pin "2") (pinfunction "D-_2") (pintype "unspecified"))
    )
    (net (code "5") (name "/MDP") (class "Default")
      (node (ref "SW21") (pin "4") (pinfunction "4_4") (pintype "input"))
      (node (ref "USB5") (pin "3") (pinfunction "D+_3") (pintype "unspecified"))
    )
    (net (code "6") (name "/OVCUR") (class "Default")
      (node (ref "R99") (pin "1") (pinfunction "1_1") (pintype "input"))
      (node (ref "U35") (pin "26") (pinfunction "OVCUR#_26") (pintype "unspecified"))
      (node (ref "U38") (pin "3") (pinfunction "FAULT#_3") (pintype "unspecified"))
    )
    (net (code "7") (name "/PWREN") (class "Default")
      (node (ref "U35") (pin "25") (pinfunction "PWREN#_25") (pintype "unspecified"))
      (node (ref "U38") (pin "4") (pinfunction "EN_4") (pintype "unspecified"))
    )
    (net (code "8") (name "/SWCLK") (class "Default")
      (node (ref "H2") (pin "1") (pinfunction "1_1") (pintype "unspecified"))
      (node (ref "U28") (pin "33") (pinfunction "SWCLK_33") (pintype "unspecified"))
    )
    (net (code "9") (name "/SWDATA") (class "Default")
      (node (ref "H2") (pin "2") (pinfunction "2_2") (pintype "unspecified"))
      (node (ref "U28") (pin "34") (pinfunction "SWDIO_34") (pintype "unspecified"))
    )
    (net (code "10") (name "/VBAT") (class "Default")
      (node (ref "BT6") (pin "1") (pinfunction "1_1") (pintype "input"))
      (node (ref "C63") (pin "1") (pinfunction "1_1") (pintype "input"))
      (node (ref "U19") (pin "6") (pinfunction "VBAT_6") (pintype "unspecified"))
    )
    (net (code "11") (name "/VCCBAT") (class "Default")
      (node (ref "C123") (pin "1") (pinfunction "1_1") (pintype "input"))
      (node (ref "C124") (pin "2") (pinfunction "2_2") (pintype "input"))
      (node (ref "FB1") (pin "1") (pinfunction "1_1") (pintype "unspecified"))
      (node (ref "U36") (pin "14") (pinfunction "VDDIO_14") (pintype "unspecified"))
      (node (ref "U36") (pin "16") (pinfunction "Vin_16") (pintype "unspecified"))
    )
    (net (code "12") (name "/VREG_AVDD") (class "Default")
      (node (ref "C103") (pin "2") (pinfunction "2_2") (pintype "input"))
      (node (ref "C35") (pin "2") (pinfunction "2_2") (pintype "input"))
      (node (ref "L29") (pin "1") (pinfunction "1_1") (pintype "unspecified"))
      (node (ref "U28") (pin "61") (pinfunction "VREG_AVDD_61") (pintype "unspecified"))
    )
    (net (code "13") (name "/VREG_VIN") (class "Default")
      (node (ref "C119") (pin "1") (pinfunction "1_1") (pintype "unspecified"))
      (node (ref "R88") (pin "2") (pinfunction "2_2") (pintype "input"))
      (node (ref "U28") (pin "64") (pinfunction "VREG_VIN_64") (pintype "unspecified"))
    )
    (net (code "14") (name "/VUSBOUT") (class "Default")
      (node (ref "C85") (pin "1") (pinfunction "1_1") (pintype "input"))
      (node (ref "U38") (pin "1") (pinfunction "OUT_1") (pintype "unspecified"))
      (node (ref "USB3") (pin "1") (pinfunction "VCC_1") (pintype "input"))
      (node (ref "USB3") (pin "5") (pinfunction "VCC_5") (pintype "input"))
      (node (ref "USB4") (pin "1") (pinfunction "VCC_1") (pintype "input"))
      (node (ref "USB4") (pin "5") (pinfunction "VCC_5") (pintype "input"))
    )
    (net (code "15") (name "/XI") (class "Default")
      (node (ref "U35") (pin "3") (pinfunction "XI_3") (pintype "unspecified"))
      (node (ref "X1") (pin "3") (pinfunction "OSC2_3") (pintype "unspecified"))
    )
    (net (code "16") (name "/XO") (class "Default")
      (node (ref "U35") (pin "2") (pinfunction "XO_2") (pintype "unspecified"))
      (node (ref "X1") (pin "1") (pinfunction "OSC1_1") (pintype "unspecified"))
    )
    (net (code "17") (name "5VIN") (class "Default")
      (node (ref "SW13") (pin "2") (pinfunction "2_2") (pintype "input"))
      (node (ref "SW13") (pin "5") (pinfunction "5_5") (pintype "input"))
      (node (ref "USB2") (pin "A4") (pinfunction "VBUS_A4") (pintype "input"))
      (node (ref "USB2") (pin "A9") (pinfunction "VBUS_A9") (pintype "input"))
      (node (ref "USB2") (pin "B4") (pinfunction "VBUS_B4") (pintype "input"))
      (node (ref "USB2") (pin "B9") (pinfunction "VBUS_B9") (pintype "input"))
    )
    (net (code "18") (name "DM1") (class "Default")
      (node (ref "U35") (pin "10") (pinfunction "DM1_10") (pintype "unspecified"))
      (node (ref "USB4") (pin "2") (pinfunction "D-_2") (pintype "input"))
    )
    (net (code "19") (name "DM2") (class "Default")
      (node (ref "U35") (pin "8") (pinfunction "DM2_8") (pintype "unspecified"))
      (node (ref "USB4") (pin "6") (pinfunction "D-_6") (pintype "input"))
    )
    (net (code "20") (name "DM3") (class "Default")
      (node (ref "U35") (pin "6") (pinfunction "DM3_6") (pintype "unspecified"))
      (node (ref "USB3") (pin "2") (pinfunction "D-_2") (pintype "input"))
    )
    (net (code "21") (name "DM4") (class "Default")
      (node (ref "U35") (pin "4") (pinfunction "DM4_4") (pintype "unspecified"))
      (node (ref "USB3") (pin "6") (pinfunction "D-_6") (pintype "input"))
    )
    (net (code "22") (name "DMU") (class "Default")
      (node (ref "SW21") (pin "3") (pinfunction "3_3") (pintype "input"))
      (node (ref "U35") (pin "15") (pinfunction "DMU_15") (pintype "unspecified"))
    )
    (net (code "23") (name "DP1") (class "Default")
      (node (ref "U35") (pin "11") (pinfunction "DP1_11") (pintype "unspecified"))
      (node (ref "USB4") (pin "3") (pinfunction "D+_3") (pintype "input"))
    )
    (net (code "24") (name "DP2") (class "Default")
      (node (ref "U35") (pin "9") (pinfunction "DP2_9") (pintype "unspecified"))
      (node (ref "USB4") (pin "7") (pinfunction "D+_7") (pintype "input"))
    )
    (net (code "25") (name "DP3") (class "Default")
      (node (ref "U35") (pin "7") (pinfunction "DP3_7") (pintype "unspecified"))
      (node (ref "USB3") (pin "3") (pinfunction "D+_3") (pintype "input"))
    )
    (net (code "26") (name "DP4") (class "Default")
      (node (ref "U35") (pin "5") (pinfunction "DP4_5") (pintype "unspecified"))
      (node (ref "USB3") (pin "7") (pinfunction "D+_7") (pintype "input"))
    )
    (net (code "27") (name "DPU") (class "Default")
      (node (ref "SW21") (pin "6") (pinfunction "6_6") (pintype "input"))
      (node (ref "U35") (pin "16") (pinfunction "DPU_16") (pintype "unspecified"))
    )
    (net (code "28") (name "DVDD") (class "Default")
      (node (ref "C100") (pin "2") (pinfunction "2_2") (pintype "input"))
      (node (ref "C101") (pin "2") (pinfunction "2_2") (pintype "input"))
      (node (ref "C115") (pin "2") (pinfunction "2_2") (pintype "input"))
      (node (ref "C116") (pin "2") (pinfunction "2_2") (pintype "input"))
      (node (ref "U28") (pin "10") (pinfunction "DVDD_10") (pintype "unspecified"))
      (node (ref "U28") (pin "32") (pinfunction "DVDD_32") (pintype "unspecified"))
      (node (ref "U28") (pin "51") (pinfunction "DVDD_51") (pintype "unspecified"))
      (node (ref "U37") (pin "5") (pinfunction "OUT_5") (pintype "unspecified"))
    )
    (net (code "29") (name "GND") (class "Default")
      (node (ref "BT6") (pin "2") (pinfunction "2_2") (pintype "input"))
      (node (ref "C100") (pin "1") (pinfunction "1_1") (pintype "input"))
      (node (ref "C101") (pin "1") (pinfunction "1_1") (pintype "input"))
      (node (ref "C102") (pin "1") (pinfunction "1_1") (pintype "input"))
      (node (ref "C103") (pin "1") (pinfunction "1_1") (pintype "input"))
      (node (ref "C104") (pin "1") (pinfunction "1_1") (pintype "input"))
      (node (ref "C105") (pin "1") (pinfunction "1_1") (pintype "input"))
      (node (ref "C106") (pin "1") (pinfunction "1_1") (pintype "input"))
      (node (ref "C107") (pin "1") (pinfunction "1_1") (pintype "input"))
      (node (ref "C108") (pin "1") (pinfunction "1_1") (pintype "input"))
      (node (ref "C109") (pin "1") (pinfunction "1_1") (pintype "input"))
      (node (ref "C110") (pin "1") (pinfunction "1_1") (pintype "input"))
      (node (ref "C111") (pin "1") (pinfunction "1_1") (pintype "input"))
      (node (ref "C112") (pin "1") (pinfunction "1_1") (pintype "input"))
      (node (ref "C113") (pin "1") (pinfunction "1_1") (pintype "input"))
      (node (ref "C114") (pin "1") (pinfunction "1_1") (pintype "input"))
      (node (ref "C115") (pin "1") (pinfunction "1_1") (pintype "input"))
      (node (ref "C116") (pin "1") (pinfunction "1_1") (pintype "input"))
      (node (ref "C118") (pin "1") (pinfunction "1_1") (pintype "input"))
      (node (ref "C119") (pin "2") (pinfunction "2_2") (pintype "unspecified"))
      (node (ref "C120") (pin "1") (pinfunction "1_1") (pintype "input"))
      (node (ref "C121") (pin "2") (pinfunction "2_2") (pintype "input"))
      (node (ref "C122") (pin "2") (pinfunction "2_2") (pintype "input"))
      (node (ref "C123") (pin "2") (pinfunction "2_2") (pintype "input"))
      (node (ref "C124") (pin "1") (pinfunction "1_1") (pintype "input"))
      (node (ref "C22") (pin "1") (pinfunction "1_1") (pintype "input"))
      (node (ref "C25") (pin "1") (pinfunction "1_1") (pintype "input"))
      (node (ref "C26") (pin "1") (pinfunction "1_1") (pintype "input"))
      (node (ref "C27") (pin "1") (pinfunction "1_1") (pintype "input"))
      (node (ref "C34") (pin "2") (pinfunction "2_2") (pintype "input"))
      (node (ref "C35") (pin "1") (pinfunction "1_1") (pintype "input"))
      (node (ref "C60") (pin "1") (pinfunction "1_1") (pintype "input"))
      (node (ref "C63") (pin "2") (pinfunction "2_2") (pintype "input"))
      (node (ref "C66") (pin "1") (pinfunction "1_1") (pintype "input"))
      (node (ref "C67") (pin "1") (pinfunction "1_1") (pintype "input"))
      (node (ref "C84") (pin "2") (pinfunction "2_2") (pintype "input"))
      (node (ref "C85") (pin "2") (pinfunction "2_2") (pintype "input"))
      (node (ref "C86") (pin "1") (pinfunction "1_1") (pintype "input"))
      (node (ref "C88") (pin "1") (pinfunction "1_1") (pintype "input"))
      (node (ref "C89") (pin "1") (pinfunction "1_1") (pintype "input"))
      (node (ref "C97") (pin "2") (pinfunction "2_2") (pintype "unspecified"))
      (node (ref "C98") (pin "2") (pinfunction "2_2") (pintype "unspecified"))
      (node (ref "CARD2") (pin "10") (pinfunction "10_10") (pintype "input"))
      (node (ref "CARD2") (pin "11") (pinfunction "11_11") (pintype "input"))
      (node (ref "CARD2") (pin "12") (pinfunction "12_12") (pintype "input"))
      (node (ref "CARD2") (pin "13") (pinfunction "13_13") (pintype "input"))
      (node (ref "CARD2") (pin "6") (pinfunction "VSS_6") (pintype "input"))
      (node (ref "CN8") (pin "0") (pinfunction "0_0") (pintype "unspecified"))
      (node (ref "CN8") (pin "1") (pinfunction "1_1") (pintype "unspecified"))
      (node (ref "H2") (pin "3") (pinfunction "3_3") (pintype "unspecified"))
      (node (ref "H4") (pin "1") (pinfunction "1_1") (pintype "unspecified"))
      (node (ref "H4") (pin "2") (pinfunction "2_2") (pintype "unspecified"))
      (node (ref "H4") (pin "29") (pinfunction "29_29") (pintype "unspecified"))
      (node (ref "HDMI1") (pin "11") (pinfunction "TMDS_Clock_Shield_11") (pintype "input"))
      (node (ref "HDMI1") (pin "17") (pinfunction "DDC/CEC_Ground_17") (pintype "input"))
      (node (ref "HDMI1") (pin "2") (pinfunction "TMDS_Data2_Shield_2") (pintype "input"))
      (node (ref "HDMI1") (pin "20") (pinfunction "EH_20") (pintype "input"))
      (node (ref "HDMI1") (pin "21") (pinfunction "EH_21") (pintype "input"))
      (node (ref "HDMI1") (pin "22") (pinfunction "EH_22") (pintype "input"))
      (node (ref "HDMI1") (pin "23") (pinfunction "EH_23") (pintype "input"))
      (node (ref "HDMI1") (pin "5") (pinfunction "TMDS_Data1_Shield_5") (pintype "input"))
      (node (ref "HDMI1") (pin "8") (pinfunction "TMDS_Data0_Shield_8") (pintype "input"))
      (node (ref "L31") (pin "1") (pinfunction "1_1") (pintype "input"))
      (node (ref "LED1") (pin "1") (pinfunction "-_1") (pintype "input"))
      (node (ref "R100") (pin "1") (pinfunction "1_1") (pintype "input"))
      (node (ref "R31") (pin "1") (pinfunction "1_1") (pintype "input"))
      (node (ref "R32") (pin "1") (pinfunction "1_1") (pintype "input"))
      (node (ref "R33") (pin "1") (pinfunction "1_1") (pintype "input"))
      (node (ref "SW13") (pin "1") (pinfunction "1_1") (pintype "input"))
      (node (ref "SW13") (pin "3") (pinfunction "3_3") (pintype "input"))
      (node (ref "SW15") (pin "1") (pinfunction "1_1") (pintype "input"))
      (node (ref "SW15") (pin "3") (pinfunction "3_3") (pintype "input"))
      (node (ref "SW15") (pin "4") (pinfunction "4_4") (pintype "input"))
      (node (ref "SW22") (pin "2") (pinfunction "2_2") (pintype "unspecified"))
      (node (ref "U19") (pin "5") (pinfunction "GND_5") (pintype "unspecified"))
      (node (ref "U21") (pin "1") (pinfunction "GND_1") (pintype "input"))
      (node (ref "U24") (pin "1") (pinfunction "GND_1") (pintype "unspecified"))
      (node (ref "U27") (pin "10") (pinfunction "DEMP_10") (pintype "input"))
      (node (ref "U27") (pin "11") (pinfunction "FLT_11") (pintype "input"))
      (node (ref "U27") (pin "12") (pinfunction "SCK_12") (pintype "input"))
      (node (ref "U27") (pin "16") (pinfunction "FMT_16") (pintype "input"))
      (node (ref "U27") (pin "19") (pinfunction "DGND_19") (pintype "input"))
      (node (ref "U28") (pin "62") (pinfunction "VREG_PGND_62") (pintype "unspecified"))
      (node (ref "U28") (pin "65") (pinfunction "VREG_FB_65") (pintype "unspecified"))
      (node (ref "U28") (pin "81") (pinfunction "GND_81") (pintype "unspecified"))
      (node (ref "U33") (pin "4") (pinfunction "VSS_4") (pintype "unspecified"))
      (node (ref "U35") (pin "1") (pinfunction "GND_1") (pintype "unspecified"))
      (node (ref "U35") (pin "12") (pinfunction "GND_12") (pintype "unspecified"))
      (node (ref "U35") (pin "28") (pinfunction "GND_28") (pintype "unspecified"))
      (node (ref "U36") (pin "1") (pinfunction "Ground_1") (pintype "unspecified"))
      (node (ref "U36") (pin "11") (pinfunction "Ground_11") (pintype "unspecified"))
      (node (ref "U36") (pin "15") (pinfunction "Ground_15") (pintype "unspecified"))
      (node (ref "U36") (pin "21") (pinfunction "Ground_21") (pintype "unspecified"))
      (node (ref "U36") (pin "4") (pinfunction "Ground_4") (pintype "unspecified"))
      (node (ref "U36") (pin "7") (pinfunction "Ground_7") (pintype "unspecified"))
      (node (ref "U37") (pin "2") (pinfunction "GND_2") (pintype "unspecified"))
      (node (ref "U38") (pin "5") (pinfunction "GND_5") (pintype "unspecified"))
      (node (ref "U38") (pin "7") (pinfunction "EXP_7") (pintype "unspecified"))
      (node (ref "U6") (pin "4") (pinfunction "GND_4") (pintype "input"))
      (node (ref "U7") (pin "1") (pinfunction "GND_1") (pintype "input"))
      (node (ref "USB2") (pin "A1") (pinfunction "GND_A1") (pintype "input"))
      (node (ref "USB2") (pin "A12") (pinfunction "GND_A12") (pintype "input"))
      (node (ref "USB2") (pin "B1") (pinfunction "GND_B1") (pintype "input"))
      (node (ref "USB2") (pin "B12") (pinfunction "GND_B12") (pintype "input"))
      (node (ref "USB3") (pin "10") (pinfunction "SHELL_10") (pintype "input"))
      (node (ref "USB3") (pin "11") (pinfunction "SHELL_11") (pintype "input"))
      (node (ref "USB3") (pin "12") (pinfunction "SHELL_12") (pintype "input"))
      (node (ref "USB3") (pin "4") (pinfunction "GND_4") (pintype "input"))
      (node (ref "USB3") (pin "8") (pinfunction "GND_8") (pintype "input"))
      (node (ref "USB3") (pin "9") (pinfunction "SHELL_9") (pintype "input"))
      (node (ref "USB4") (pin "10") (pinfunction "SHELL_10") (pintype "input"))
      (node (ref "USB4") (pin "11") (pinfunction "SHELL_11") (pintype "input"))
      (node (ref "USB4") (pin "12") (pinfunction "SHELL_12") (pintype "input"))
      (node (ref "USB4") (pin "4") (pinfunction "GND_4") (pintype "input"))
      (node (ref "USB4") (pin "8") (pinfunction "GND_8") (pintype "input"))
      (node (ref "USB4") (pin "9") (pinfunction "SHELL_9") (pintype "input"))
      (node (ref "USB5") (pin "5") (pinfunction "GND_5") (pintype "unspecified"))
      (node (ref "USB5") (pin "6") (pinfunction "SH1_6") (pintype "unspecified"))
      (node (ref "USB5") (pin "7") (pinfunction "SH2_7") (pintype "unspecified"))
      (node (ref "USB5") (pin "8") (pinfunction "SH3_8") (pintype "unspecified"))
      (node (ref "USB5") (pin "9") (pinfunction "SH4_9") (pintype "unspecified"))
      (node (ref "X1") (pin "2") (pinfunction "GND_2") (pintype "unspecified"))
      (node (ref "X1") (pin "4") (pinfunction "GND_4") (pintype "unspecified"))
      (node (ref "X4") (pin "2") (pinfunction "GND_2") (pintype "unspecified"))
    )
    (net (code "30") (name "GPIO0") (class "Default")
      (node (ref "H4") (pin "5") (pinfunction "5_5") (pintype "unspecified"))
      (node (ref "U28") (pin "77") (pinfunction "GPIO0_77") (pintype "unspecified"))
    )
    (net (code "31") (name "GPIO1") (class "Default")
      (node (ref "H4") (pin "6") (pinfunction "6_6") (pintype "unspecified"))
      (node (ref "U28") (pin "78") (pinfunction "GPIO1_78") (pintype "unspecified"))
    )
    (net (code "32") (name "GPIO2") (class "Default")
      (node (ref "H4") (pin "7") (pinfunction "7_7") (pintype "unspecified"))
      (node (ref "U28") (pin "79") (pinfunction "GPIO2_79") (pintype "unspecified"))
    )
    (net (code "33") (name "GPIO3") (class "Default")
      (node (ref "H4") (pin "8") (pinfunction "8_8") (pintype "unspecified"))
      (node (ref "U28") (pin "80") (pinfunction "GPIO3_80") (pintype "unspecified"))
    )
    (net (code "34") (name "GPIO4") (class "Default")
      (node (ref "H4") (pin "9") (pinfunction "9_9") (pintype "unspecified"))
      (node (ref "U28") (pin "1") (pinfunction "GPIO4_1") (pintype "unspecified"))
    )
    (net (code "35") (name "GPIO5") (class "Default")
      (node (ref "H4") (pin "10") (pinfunction "10_10") (pintype "unspecified"))
      (node (ref "U28") (pin "2") (pinfunction "GPIO5_2") (pintype "unspecified"))
    )
    (net (code "36") (name "GPIO6") (class "Default")
      (node (ref "H4") (pin "11") (pinfunction "11_11") (pintype "unspecified"))
      (node (ref "U28") (pin "3") (pinfunction "GPIO6_3") (pintype "unspecified"))
    )
    (net (code "37") (name "GPIO7") (class "Default")
      (node (ref "H4") (pin "12") (pinfunction "12_12") (pintype "unspecified"))
      (node (ref "U28") (pin "4") (pinfunction "GPIO7_4") (pintype "unspecified"))
    )
    (net (code "38") (name "GPIO8") (class "Default")
      (node (ref "U28") (pin "6") (pinfunction "GPIO8_6") (pintype "unspecified"))
      (node (ref "U7") (pin "3") (pinfunction "RXD_3") (pintype "input"))
    )
    (net (code "39") (name "GPIO9") (class "Default")
      (node (ref "U28") (pin "7") (pinfunction "GPIO9_7") (pintype "unspecified"))
      (node (ref "U7") (pin "2") (pinfunction "TXD_2") (pintype "input"))
    )
    (net (code "40") (name "GPIO10") (class "Default")
      (node (ref "U27") (pin "13") (pinfunction "BCK_13") (pintype "input"))
      (node (ref "U28") (pin "8") (pinfunction "GPIO10_8") (pintype "unspecified"))
    )
    (net (code "41") (name "GPIO11") (class "Default")
      (node (ref "U27") (pin "15") (pinfunction "LRCK_15") (pintype "input"))
      (node (ref "U28") (pin "9") (pinfunction "GPIO11_9") (pintype "unspecified"))
    )
    (net (code "42") (name "GPIO12") (class "Default")
      (node (ref "R68") (pin "1") (pinfunction "1_1") (pintype "input"))
      (node (ref "U28") (pin "11") (pinfunction "GPIO12_11") (pintype "unspecified"))
    )
    (net (code "43") (name "GPIO13") (class "Default")
      (node (ref "R67") (pin "1") (pinfunction "1_1") (pintype "input"))
      (node (ref "U28") (pin "12") (pinfunction "GPIO13_12") (pintype "unspecified"))
    )
    (net (code "44") (name "GPIO14") (class "Default")
      (node (ref "R66") (pin "1") (pinfunction "1_1") (pintype "input"))
      (node (ref "U28") (pin "13") (pinfunction "GPIO14_13") (pintype "unspecified"))
    )
    (net (code "45") (name "GPIO15") (class "Default")
      (node (ref "R65") (pin "1") (pinfunction "1_1") (pintype "input"))
      (node (ref "U28") (pin "14") (pinfunction "GPIO15_14") (pintype "unspecified"))
    )
    (net (code "46") (name "GPIO16") (class "Default")
      (node (ref "R64") (pin "1") (pinfunction "1_1") (pintype "input"))
      (node (ref "U28") (pin "16") (pinfunction "GPIO16_16") (pintype "unspecified"))
    )
    (net (code "47") (name "GPIO17") (class "Default")
      (node (ref "R63") (pin "1") (pinfunction "1_1") (pintype "input"))
      (node (ref "U28") (pin "17") (pinfunction "GPIO17_17") (pintype "unspecified"))
    )
    (net (code "48") (name "GPIO18") (class "Default")
      (node (ref "R62") (pin "1") (pinfunction "1_1") (pintype "input"))
      (node (ref "U28") (pin "18") (pinfunction "GPIO18_18") (pintype "unspecified"))
    )
    (net (code "49") (name "GPIO19") (class "Default")
      (node (ref "R61") (pin "1") (pinfunction "1_1") (pintype "input"))
      (node (ref "U28") (pin "19") (pinfunction "GPIO19_19") (pintype "unspecified"))
    )
    (net (code "50") (name "GPIO20") (class "Default")
      (node (ref "CN8") (pin "3") (pinfunction "3_3") (pintype "unspecified"))
      (node (ref "H4") (pin "28") (pinfunction "28_28") (pintype "unspecified"))
      (node (ref "R52") (pin "1") (pinfunction "1_1") (pintype "input"))
      (node (ref "U19") (pin "7") (pinfunction "SDA_7") (pintype "bidirectional"))
      (node (ref "U28") (pin "20") (pinfunction "GPIO20_20") (pintype "unspecified"))
    )
    (net (code "51") (name "GPIO21") (class "Default")
      (node (ref "CN8") (pin "4") (pinfunction "4_4") (pintype "unspecified"))
      (node (ref "H4") (pin "30") (pinfunction "30_30") (pintype "unspecified"))
      (node (ref "R53") (pin "1") (pinfunction "1_1") (pintype "input"))
      (node (ref "U19") (pin "8") (pinfunction "SCL_8") (pintype "unspecified"))
      (node (ref "U28") (pin "21") (pinfunction "GPIO21_21") (pintype "unspecified"))
    )
    (net (code "52") (name "GPIO22") (class "Default")
      (node (ref "U27") (pin "14") (pinfunction "DIN_14") (pintype "input"))
      (node (ref "U28") (pin "22") (pinfunction "GPIO22_22") (pintype "unspecified"))
    )
    (net (code "53") (name "GPIO23") (class "Default")
      (node (ref "U28") (pin "23") (pinfunction "GPIO23_23") (pintype "unspecified"))
      (node (ref "U36") (pin "12") (pinfunction "Wi-Fi_on_12") (pintype "unspecified"))
      (node (ref "U36") (pin "13") (pinfunction "Bluetooth_on_13") (pintype "unspecified"))
    )
    (net (code "54") (name "GPIO24") (class "Default")
      (node (ref "R90") (pin "1") (pinfunction "1_1") (pintype "input"))
      (node (ref "R96") (pin "1") (pinfunction "1_1") (pintype "input"))
      (node (ref "U28") (pin "25") (pinfunction "GPIO24_25") (pintype "unspecified"))
      (node (ref "U36") (pin "5") (pinfunction "gSPI_Data_In_5") (pintype "unspecified"))
    )
    (net (code "55") (name "GPIO25") (class "Default")
      (node (ref "H5") (pin "1") (pinfunction "1_1") (pintype "unspecified"))
      (node (ref "U28") (pin "26") (pinfunction "GPIO25_26") (pintype "unspecified"))
      (node (ref "U36") (pin "9") (pinfunction "gSPICS_9") (pintype "unspecified"))
    )
    (net (code "56") (name "GPIO26") (class "Default")
      (node (ref "H4") (pin "14") (pinfunction "14_14") (pintype "unspecified"))
      (node (ref "U28") (pin "27") (pinfunction "GPIO26_27") (pintype "unspecified"))
    )
    (net (code "57") (name "GPIO27") (class "Default")
      (node (ref "R95") (pin "1") (pinfunction "1_1") (pintype "input"))
      (node (ref "U19") (pin "1") (pinfunction "32kHz_1") (pintype "unspecified"))
      (node (ref "U28") (pin "28") (pinfunction "GPIO27_28") (pintype "unspecified"))
    )
    (net (code "58") (name "GPIO28") (class "Default")
      (node (ref "CARD2") (pin "7") (pinfunction "DAT0_7") (pintype "input"))
      (node (ref "U28") (pin "36") (pinfunction "GPIO28_36") (pintype "unspecified"))
    )
    (net (code "59") (name "GPIO29") (class "Default")
      (node (ref "U28") (pin "37") (pinfunction "GPIO29_37") (pintype "unspecified"))
      (node (ref "U36") (pin "3") (pinfunction "gSPI_SCLK_3") (pintype "unspecified"))
    )
    (net (code "60") (name "GPIO30") (class "Default")
      (node (ref "CARD2") (pin "5") (pinfunction "CLX_5") (pintype "input"))
      (node (ref "U28") (pin "38") (pinfunction "GPIO30_38") (pintype "unspecified"))
    )
    (net (code "61") (name "GPIO31") (class "Default")
      (node (ref "CARD2") (pin "3") (pinfunction "CMD_3") (pintype "input"))
      (node (ref "U28") (pin "39") (pinfunction "GPIO31_39") (pintype "unspecified"))
    )
    (net (code "62") (name "GPIO32") (class "Default")
      (node (ref "R94") (pin "1") (pinfunction "1_1") (pintype "input"))
      (node (ref "U19") (pin "3") (pinfunction "INT#/SQW_3") (pintype "bidirectional"))
      (node (ref "U28") (pin "40") (pinfunction "GPIO32_40") (pintype "unspecified"))
    )
    (net (code "63") (name "GPIO33") (class "Default")
      (node (ref "CARD2") (pin "2") (pinfunction "CD/DAT3_2") (pintype "input"))
      (node (ref "U28") (pin "42") (pinfunction "GPIO33_42") (pintype "unspecified"))
    )
    (net (code "64") (name "GPIO34") (class "Default")
      (node (ref "H4") (pin "13") (pinfunction "13_13") (pintype "unspecified"))
      (node (ref "U28") (pin "43") (pinfunction "GPIO34_43") (pintype "unspecified"))
    )
    (net (code "65") (name "GPIO35") (class "Default")
      (node (ref "H4") (pin "16") (pinfunction "16_16") (pintype "unspecified"))
      (node (ref "U28") (pin "44") (pinfunction "GPIO35_44") (pintype "unspecified"))
    )
    (net (code "66") (name "GPIO36") (class "Default")
      (node (ref "H4") (pin "15") (pinfunction "15_15") (pintype "unspecified"))
      (node (ref "U28") (pin "45") (pinfunction "GPIO36_45") (pintype "unspecified"))
    )
    (net (code "67") (name "GPIO37") (class "Default")
      (node (ref "H4") (pin "18") (pinfunction "18_18") (pintype "unspecified"))
      (node (ref "U28") (pin "46") (pinfunction "GPIO37_46") (pintype "unspecified"))
    )
    (net (code "68") (name "GPIO38") (class "Default")
      (node (ref "H4") (pin "17") (pinfunction "17_17") (pintype "unspecified"))
      (node (ref "U28") (pin "47") (pinfunction "GPIO38_47") (pintype "unspecified"))
    )
    (net (code "69") (name "GPIO39") (class "Default")
      (node (ref "H4") (pin "20") (pinfunction "20_20") (pintype "unspecified"))
      (node (ref "U28") (pin "48") (pinfunction "GPIO39_48") (pintype "unspecified"))
    )
    (net (code "70") (name "GPIO40") (class "Default")
      (node (ref "H4") (pin "19") (pinfunction "19_19") (pintype "unspecified"))
      (node (ref "U28") (pin "49") (pinfunction "GPIO40_ADC0_49") (pintype "unspecified"))
    )
    (net (code "71") (name "GPIO41") (class "Default")
      (node (ref "H4") (pin "22") (pinfunction "22_22") (pintype "unspecified"))
      (node (ref "U28") (pin "52") (pinfunction "GPIO41_ADC1_52") (pintype "unspecified"))
    )
    (net (code "72") (name "GPIO42") (class "Default")
      (node (ref "H4") (pin "21") (pinfunction "21_21") (pintype "unspecified"))
      (node (ref "U28") (pin "53") (pinfunction "GPIO42_ADC2_53") (pintype "unspecified"))
    )
    (net (code "73") (name "GPIO43") (class "Default")
      (node (ref "H4") (pin "24") (pinfunction "24_24") (pintype "unspecified"))
      (node (ref "U28") (pin "54") (pinfunction "GPIO43_ADC3_54") (pintype "unspecified"))
    )
    (net (code "74") (name "GPIO44") (class "Default")
      (node (ref "H4") (pin "23") (pinfunction "23_23") (pintype "unspecified"))
      (node (ref "U28") (pin "55") (pinfunction "GPIO44_ADC4_55") (pintype "unspecified"))
    )
    (net (code "75") (name "GPIO45") (class "Default")
      (node (ref "H4") (pin "26") (pinfunction "26_26") (pintype "unspecified"))
      (node (ref "U28") (pin "56") (pinfunction "GPIO45_ADC5_56") (pintype "unspecified"))
    )
    (net (code "76") (name "GPIO46") (class "Default")
      (node (ref "H4") (pin "25") (pinfunction "25_25") (pintype "unspecified"))
      (node (ref "U28") (pin "57") (pinfunction "GPIO46_ADC6_57") (pintype "unspecified"))
    )
    (net (code "77") (name "HEARTBEAT") (class "Default")
      (node (ref "H5") (pin "2") (pinfunction "2_2") (pintype "unspecified"))
      (node (ref "R3") (pin "1") (pinfunction "1_1") (pintype "input"))
    )
    (net (code "78") (name "LED1") (class "Default")
      (node (ref "PORT3") (pin "1") (pinfunction "A_1") (pintype "unspecified"))
      (node (ref "PORT4") (pin "2") (pinfunction "K_2") (pintype "unspecified"))
      (node (ref "R58") (pin "2") (pinfunction "2_2") (pintype "input"))
    )
    (net (code "79") (name "LED2") (class "Default")
      (node (ref "PORT1") (pin "1") (pinfunction "A_1") (pintype "unspecified"))
      (node (ref "PORT2") (pin "2") (pinfunction "K_2") (pintype "unspecified"))
      (node (ref "R57") (pin "2") (pinfunction "2_2") (pintype "input"))
    )
    (net (code "80") (name "LED4") (class "Default")
      (node (ref "PORT1") (pin "2") (pinfunction "K_2") (pintype "unspecified"))
      (node (ref "PORT2") (pin "1") (pinfunction "A_1") (pintype "unspecified"))
      (node (ref "PORT3") (pin "2") (pinfunction "K_2") (pintype "unspecified"))
      (node (ref "PORT4") (pin "1") (pinfunction "A_1") (pintype "unspecified"))
      (node (ref "R59") (pin "1") (pinfunction "1_1") (pintype "input"))
      (node (ref "U35") (pin "22") (pinfunction "LED4/SDA_22") (pintype "unspecified"))
    )
    (net (code "81") (name "Net-(ACTIVE-K)") (class "Default")
      (node (ref "ACTIVE") (pin "1") (pinfunction "K_1") (pintype "input"))
      (node (ref "R59") (pin "2") (pinfunction "2_2") (pintype "input"))
    )
    (net (code "82") (name "Net-(C95-Pad2)") (class "Default")
      (node (ref "C95") (pin "2") (pinfunction "2_2") (pintype "input"))
      (node (ref "CN5") (pin "3") (pinfunction "3_3") (pintype "input"))
      (node (ref "R70") (pin "1") (pinfunction "1_1") (pintype "input"))
    )
    (net (code "83") (name "Net-(C96-Pad2)") (class "Default")
      (node (ref "C96") (pin "2") (pinfunction "2_2") (pintype "input"))
      (node (ref "CN5") (pin "2") (pinfunction "2_2") (pintype "input"))
      (node (ref "R69") (pin "1") (pinfunction "1_1") (pintype "input"))
    )
    (net (code "84") (name "Net-(C118-Pad2)") (class "Default")
      (node (ref "C118") (pin "2") (pinfunction "2_2") (pintype "input"))
      (node (ref "L29") (pin "2") (pinfunction "2_2") (pintype "unspecified"))
      (node (ref "R79") (pin "1") (pinfunction "1_1") (pintype "input"))
    )
    (net (code "85") (name "Net-(CARD2-VDD)") (class "Default")
      (node (ref "C120") (pin "2") (pinfunction "2_2") (pintype "input"))
      (node (ref "C27") (pin "2") (pinfunction "2_2") (pintype "input"))
      (node (ref "CARD2") (pin "4") (pinfunction "VDD_4") (pintype "input"))
      (node (ref "R29") (pin "1") (pinfunction "1_1") (pintype "input"))
    )
    (net (code "86") (name "Net-(D1-K)") (class "Default")
      (node (ref "D1") (pin "1") (pinfunction "K_1") (pintype "unspecified"))
      (node (ref "HDMI1") (pin "18") (pinfunction "+5V_Power_18") (pintype "input"))
    )
    (net (code "87") (name "Net-(D2-A)") (class "Default")
      (node (ref "D2") (pin "2") (pinfunction "A_2") (pintype "unspecified"))
      (node (ref "USB5") (pin "1") (pinfunction "VBUS_1") (pintype "unspecified"))
    )
    (net (code "88") (name "Net-(HDMI1-TMDS_Clock+)") (class "Default")
      (node (ref "HDMI1") (pin "10") (pinfunction "TMDS_Clock+_10") (pintype "input"))
      (node (ref "R67") (pin "2") (pinfunction "2_2") (pintype "input"))
    )
    (net (code "89") (name "Net-(HDMI1-TMDS_Clock-)") (class "Default")
      (node (ref "HDMI1") (pin "12") (pinfunction "TMDS_Clock-_12") (pintype "input"))
      (node (ref "R68") (pin "2") (pinfunction "2_2") (pintype "input"))
    )
    (net (code "90") (name "Net-(HDMI1-TMDS_Data0+)") (class "Default")
      (node (ref "HDMI1") (pin "7") (pinfunction "TMDS_Data0+_7") (pintype "input"))
      (node (ref "R65") (pin "2") (pinfunction "2_2") (pintype "input"))
    )
    (net (code "91") (name "Net-(HDMI1-TMDS_Data1+)") (class "Default")
      (node (ref "HDMI1") (pin "4") (pinfunction "TMDS_Data1+_4") (pintype "input"))
      (node (ref "R63") (pin "2") (pinfunction "2_2") (pintype "input"))
    )
    (net (code "92") (name "Net-(HDMI1-TMDS_Data1-)") (class "Default")
      (node (ref "HDMI1") (pin "6") (pinfunction "TMDS_Data1-_6") (pintype "input"))
      (node (ref "R64") (pin "2") (pinfunction "2_2") (pintype "input"))
    )
    (net (code "93") (name "Net-(HDMI1-TMDS_Data2+)") (class "Default")
      (node (ref "HDMI1") (pin "1") (pinfunction "TMDS_Data2+_1") (pintype "input"))
      (node (ref "R61") (pin "2") (pinfunction "2_2") (pintype "input"))
    )
    (net (code "94") (name "Net-(HDMI1-TMDS_Data2-)") (class "Default")
      (node (ref "HDMI1") (pin "3") (pinfunction "TMDS_Data2-_3") (pintype "input"))
      (node (ref "R62") (pin "2") (pinfunction "2_2") (pintype "input"))
    )
    (net (code "95") (name "Net-(HDMI1-TMDS_Data_0-)") (class "Default")
      (node (ref "HDMI1") (pin "9") (pinfunction "TMDS_Data_0-_9") (pintype "input"))
      (node (ref "R66") (pin "2") (pinfunction "2_2") (pintype "input"))
    )
    (net (code "96") (name "Net-(LED1-+)") (class "Default")
      (node (ref "LED1") (pin "2") (pinfunction "+_2") (pintype "input"))
      (node (ref "R3") (pin "2") (pinfunction "2_2") (pintype "input"))
    )
    (net (code "97") (name "Net-(R4-Pad2)") (class "Default")
      (node (ref "R4") (pin "2") (pinfunction "2_2") (pintype "input"))
      (node (ref "SW22") (pin "1") (pinfunction "1_1") (pintype "unspecified"))
    )
    (net (code "98") (name "Net-(R33-Pad2)") (class "Default")
      (node (ref "R33") (pin "2") (pinfunction "2_2") (pintype "input"))
      (node (ref "USB2") (pin "1") (pinfunction "EP_1") (pintype "input"))
      (node (ref "USB2") (pin "2") (pinfunction "EP_2") (pintype "input"))
      (node (ref "USB2") (pin "3") (pinfunction "EP_3") (pintype "input"))
      (node (ref "USB2") (pin "4") (pinfunction "EP_4") (pintype "input"))
    )
    (net (code "99") (name "Net-(U24-RESET)") (class "Default")
      (node (ref "R60") (pin "2") (pinfunction "2_2") (pintype "input"))
      (node (ref "U24") (pin "2") (pinfunction "RESET_2") (pintype "unspecified"))
    )
    (net (code "100") (name "Net-(U27-CAPM)") (class "Default")
      (node (ref "C81") (pin "2") (pinfunction "2_2") (pintype "input"))
      (node (ref "U27") (pin "4") (pinfunction "CAPM_4") (pintype "input"))
    )
    (net (code "101") (name "Net-(U27-CAPP)") (class "Default")
      (node (ref "C81") (pin "1") (pinfunction "1_1") (pintype "input"))
      (node (ref "U27") (pin "2") (pinfunction "CAPP_2") (pintype "input"))
    )
    (net (code "102") (name "Net-(U27-LDOO)") (class "Default")
      (node (ref "C97") (pin "1") (pinfunction "1_1") (pintype "unspecified"))
      (node (ref "C98") (pin "1") (pinfunction "1_1") (pintype "unspecified"))
      (node (ref "U27") (pin "18") (pinfunction "LDOO_18") (pintype "input"))
    )
    (net (code "103") (name "Net-(U27-OUTL)") (class "Default")
      (node (ref "R70") (pin "2") (pinfunction "2_2") (pintype "input"))
      (node (ref "U27") (pin "6") (pinfunction "OUTL_6") (pintype "input"))
    )
    (net (code "104") (name "Net-(U27-OUTR)") (class "Default")
      (node (ref "R69") (pin "2") (pinfunction "2_2") (pintype "input"))
      (node (ref "U27") (pin "7") (pinfunction "OUTR_7") (pintype "input"))
    )
    (net (code "105") (name "Net-(U27-VNEG)") (class "Default")
      (node (ref "C93") (pin "1") (pinfunction "1_1") (pintype "input"))
      (node (ref "U27") (pin "5") (pinfunction "VNEG_5") (pintype "input"))
    )
    (net (code "106") (name "Net-(U28-XIN)") (class "Default")
      (node (ref "U28") (pin "30") (pinfunction "XIN_30") (pintype "unspecified"))
      (node (ref "X4") (pin "3") (pinfunction "OUT_3") (pintype "unspecified"))
    )
    (net (code "107") (name "Net-(U35-LED1{slash}PSELF)") (class "Default")
      (node (ref "R58") (pin "1") (pinfunction "1_1") (pintype "input"))
      (node (ref "U35") (pin "23") (pinfunction "LED1/PSELF_23") (pintype "unspecified"))
    )
    (net (code "108") (name "Net-(U35-LED2{slash}PGANG)") (class "Default")
      (node (ref "R57") (pin "1") (pinfunction "1_1") (pintype "input"))
      (node (ref "U35") (pin "24") (pinfunction "LED2/PGANG_24") (pintype "unspecified"))
    )
    (net (code "109") (name "Net-(U36-GPIO0)") (class "Default")
      (node (ref "H5") (pin "3") (pinfunction "3_3") (pintype "unspecified"))
      (node (ref "U36") (pin "8") (pinfunction "GPIO0_8") (pintype "unspecified"))
    )
    (net (code "110") (name "Net-(U36-gSPI_Data_out)") (class "Default")
      (node (ref "R90") (pin "2") (pinfunction "2_2") (pintype "input"))
      (node (ref "U36") (pin "6") (pinfunction "gSPI_Data_out_6") (pintype "unspecified"))
    )
    (net (code "111") (name "Net-(U36-nIRQ)") (class "Default")
      (node (ref "R96") (pin "2") (pinfunction "2_2") (pintype "input"))
      (node (ref "U36") (pin "10") (pinfunction "nIRQ_10") (pintype "unspecified"))
    )
    (net (code "112") (name "Net-(U38-ILIM)") (class "Default")
      (node (ref "R100") (pin "2") (pinfunction "2_2") (pintype "input"))
      (node (ref "U38") (pin "2") (pinfunction "ILIM_2") (pintype "unspecified"))
    )
    (net (code "113") (name "Net-(USB2-CC1)") (class "Default")
      (node (ref "R32") (pin "2") (pinfunction "2_2") (pintype "input"))
      (node (ref "USB2") (pin "A5") (pinfunction "CC1_A5") (pintype "input"))
    )
    (net (code "114") (name "Net-(USB2-CC2)") (class "Default")
      (node (ref "R31") (pin "2") (pinfunction "2_2") (pintype "input"))
      (node (ref "USB2") (pin "B5") (pinfunction "CC2_B5") (pintype "input"))
    )
    (net (code "115") (name "PSRAM_SS") (class "Default")
      (node (ref "R97") (pin "1") (pinfunction "1_1") (pintype "input"))
      (node (ref "U28") (pin "58") (pinfunction "GPIO47_ADC7_58") (pintype "unspecified"))
      (node (ref "U33") (pin "1") (pinfunction "CE#_1") (pintype "unspecified"))
    )
    (net (code "116") (name "QSPI_SCLK") (class "Default")
      (node (ref "U28") (pin "71") (pinfunction "QSPI_SCLK_71") (pintype "unspecified"))
      (node (ref "U33") (pin "6") (pinfunction "SCLK_6") (pintype "unspecified"))
      (node (ref "U6") (pin "6") (pinfunction "CLK_6") (pintype "input"))
    )
    (net (code "117") (name "QSPI_SD0") (class "Default")
      (node (ref "U28") (pin "72") (pinfunction "QSPI_SD0_72") (pintype "unspecified"))
      (node (ref "U33") (pin "5") (pinfunction "SI/SIO[0]_5") (pintype "unspecified"))
      (node (ref "U6") (pin "5") (pinfunction "DI_5") (pintype "input"))
    )
    (net (code "118") (name "QSPI_SD1") (class "Default")
      (node (ref "U28") (pin "74") (pinfunction "QSPI_SD1_74") (pintype "unspecified"))
      (node (ref "U33") (pin "2") (pinfunction "SO/SIO[1]_2") (pintype "unspecified"))
      (node (ref "U6") (pin "2") (pinfunction "DO_2") (pintype "input"))
    )
    (net (code "119") (name "QSPI_SD2") (class "Default")
      (node (ref "U28") (pin "73") (pinfunction "QSPI_SD2_73") (pintype "unspecified"))
      (node (ref "U33") (pin "3") (pinfunction "SIO[2]_3") (pintype "unspecified"))
      (node (ref "U6") (pin "3") (pinfunction "IO2_3") (pintype "input"))
    )
    (net (code "120") (name "QSPI_SD3") (class "Default")
      (node (ref "U28") (pin "70") (pinfunction "QSPI_SD3_70") (pintype "unspecified"))
      (node (ref "U33") (pin "7") (pinfunction "SIO[3]_7") (pintype "unspecified"))
      (node (ref "U6") (pin "7") (pinfunction "IO3_7") (pintype "input"))
    )
    (net (code "121") (name "QSPI_SS") (class "Default")
      (node (ref "R4") (pin "1") (pinfunction "1_1") (pintype "input"))
      (node (ref "R98") (pin "1") (pinfunction "1_1") (pintype "input"))
      (node (ref "U28") (pin "75") (pinfunction "QSPI_SS_75") (pintype "unspecified"))
      (node (ref "U6") (pin "1") (pinfunction "CS#_1") (pintype "input"))
    )
    (net (code "122") (name "RESET") (class "Default")
      (node (ref "R60") (pin "1") (pinfunction "1_1") (pintype "input"))
      (node (ref "SW15") (pin "2") (pinfunction "2_2") (pintype "input"))
      (node (ref "U28") (pin "35") (pinfunction "RUN_35") (pintype "unspecified"))
      (node (ref "U35") (pin "17") (pinfunction "RESET#/CDP_17") (pintype "unspecified"))
    )
    (net (code "123") (name "USB-DM") (class "Default")
      (node (ref "U7") (pin "6") (pinfunction "D-_6") (pintype "input"))
      (node (ref "USB2") (pin "A7") (pinfunction "DN1_A7") (pintype "input"))
      (node (ref "USB2") (pin "B7") (pinfunction "DN2_B7") (pintype "input"))
    )
    (net (code "124") (name "USB-DP") (class "Default")
      (node (ref "U7") (pin "5") (pinfunction "D+_5") (pintype "input"))
      (node (ref "USB2") (pin "A6") (pinfunction "DP1_A6") (pintype "input"))
      (node (ref "USB2") (pin "B6") (pinfunction "DP2_B6") (pintype "input"))
    )
    (net (code "125") (name "USB_HOST_DM") (class "Default")
      (node (ref "SW21") (pin "2") (pinfunction "2_2") (pintype "input"))
      (node (ref "U28") (pin "66") (pinfunction "USB_DM_66") (pintype "unspecified"))
    )
    (net (code "126") (name "USB_HOST_DP") (class "Default")
      (node (ref "SW21") (pin "5") (pinfunction "5_5") (pintype "input"))
      (node (ref "U28") (pin "67") (pinfunction "USB_DP_67") (pintype "unspecified"))
    )
    (net (code "127") (name "VCC") (class "Default")
      (node (ref "ACTIVE") (pin "2") (pinfunction "A_2") (pintype "input"))
      (node (ref "C102") (pin "2") (pinfunction "2_2") (pintype "input"))
      (node (ref "C104") (pin "2") (pinfunction "2_2") (pintype "input"))
      (node (ref "C105") (pin "2") (pinfunction "2_2") (pintype "input"))
      (node (ref "C106") (pin "2") (pinfunction "2_2") (pintype "input"))
      (node (ref "C107") (pin "2") (pinfunction "2_2") (pintype "input"))
      (node (ref "C108") (pin "2") (pinfunction "2_2") (pintype "input"))
      (node (ref "C109") (pin "2") (pinfunction "2_2") (pintype "input"))
      (node (ref "C110") (pin "2") (pinfunction "2_2") (pintype "input"))
      (node (ref "C111") (pin "2") (pinfunction "2_2") (pintype "input"))
      (node (ref "C112") (pin "2") (pinfunction "2_2") (pintype "input"))
      (node (ref "C113") (pin "2") (pinfunction "2_2") (pintype "input"))
      (node (ref "C114") (pin "2") (pinfunction "2_2") (pintype "input"))
      (node (ref "C22") (pin "2") (pinfunction "2_2") (pintype "input"))
      (node (ref "C26") (pin "2") (pinfunction "2_2") (pintype "input"))
      (node (ref "C34") (pin "1") (pinfunction "1_1") (pintype "input"))
      (node (ref "C60") (pin "2") (pinfunction "2_2") (pintype "input"))
      (node (ref "C66") (pin "2") (pinfunction "2_2") (pintype "input"))
      (node (ref "C84") (pin "1") (pinfunction "1_1") (pintype "input"))
      (node (ref "C86") (pin "2") (pinfunction "2_2") (pintype "input"))
      (node (ref "C88") (pin "2") (pinfunction "2_2") (pintype "input"))
      (node (ref "C89") (pin "2") (pinfunction "2_2") (pintype "input"))
      (node (ref "CN8") (pin "2") (pinfunction "2_2") (pintype "unspecified"))
      (node (ref "FB1") (pin "2") (pinfunction "2_2") (pintype "unspecified"))
      (node (ref "H4") (pin "3") (pinfunction "3_3") (pintype "unspecified"))
      (node (ref "H4") (pin "4") (pinfunction "4_4") (pintype "unspecified"))
      (node (ref "L30") (pin "2") (pinfunction "2_2") (pintype "input"))
      (node (ref "R29") (pin "2") (pinfunction "2_2") (pintype "input"))
      (node (ref "R52") (pin "2") (pinfunction "2_2") (pintype "input"))
      (node (ref "R53") (pin "2") (pinfunction "2_2") (pintype "input"))
      (node (ref "R79") (pin "2") (pinfunction "2_2") (pintype "input"))
      (node (ref "R88") (pin "1") (pinfunction "1_1") (pintype "input"))
      (node (ref "R94") (pin "2") (pinfunction "2_2") (pintype "input"))
      (node (ref "R95") (pin "2") (pinfunction "2_2") (pintype "input"))
      (node (ref "R97") (pin "2") (pinfunction "2_2") (pintype "input"))
      (node (ref "R98") (pin "2") (pinfunction "2_2") (pintype "input"))
      (node (ref "U19") (pin "2") (pinfunction "VCC_2") (pintype "unspecified"))
      (node (ref "U19") (pin "4") (pinfunction "RST#_4") (pintype "bidirectional"))
      (node (ref "U21") (pin "2") (pinfunction "VOUT_2") (pintype "input"))
      (node (ref "U21") (pin "4") (pinfunction "VOUT_4") (pintype "input"))
      (node (ref "U24") (pin "3") (pinfunction "VDD_3") (pintype "unspecified"))
      (node (ref "U27") (pin "17") (pinfunction "XSMT_17") (pintype "input"))
      (node (ref "U27") (pin "20") (pinfunction "DVDD_20") (pintype "input"))
      (node (ref "U28") (pin "15") (pinfunction "IOVDD_15") (pintype "unspecified"))
      (node (ref "U28") (pin "24") (pinfunction "IOVDD_24") (pintype "unspecified"))
      (node (ref "U28") (pin "29") (pinfunction "IOVDD_29") (pintype "unspecified"))
      (node (ref "U28") (pin "41") (pinfunction "IOVDD_41") (pintype "unspecified"))
      (node (ref "U28") (pin "5") (pinfunction "IOVDD_5") (pintype "unspecified"))
      (node (ref "U28") (pin "50") (pinfunction "IOVDD_50") (pintype "unspecified"))
      (node (ref "U28") (pin "59") (pinfunction "ADC_AVDD_59") (pintype "unspecified"))
      (node (ref "U28") (pin "60") (pinfunction "IOVDD_60") (pintype "unspecified"))
      (node (ref "U28") (pin "68") (pinfunction "USB_OTP_VDD_68") (pintype "unspecified"))
      (node (ref "U28") (pin "69") (pinfunction "QSPI_IOVDD_69") (pintype "unspecified"))
      (node (ref "U28") (pin "76") (pinfunction "IOVDD_76") (pintype "unspecified"))
      (node (ref "U33") (pin "8") (pinfunction "VDD_8") (pintype "unspecified"))
      (node (ref "U35") (pin "13") (pinfunction "VDD33_13") (pintype "unspecified"))
      (node (ref "U35") (pin "21") (pinfunction "VDD33_21") (pintype "unspecified"))
      (node (ref "U37") (pin "1") (pinfunction "IN_1") (pintype "unspecified"))
      (node (ref "U37") (pin "3") (pinfunction "EN_3") (pintype "unspecified"))
      (node (ref "U6") (pin "8") (pinfunction "VCC_8") (pintype "input"))
      (node (ref "U7") (pin "16") (pinfunction "VCC_16") (pintype "input"))
      (node (ref "U7") (pin "4") (pinfunction "V3_4") (pintype "input"))
      (node (ref "X4") (pin "1") (pinfunction "TRI-STATE_1") (pintype "unspecified"))
      (node (ref "X4") (pin "4") (pinfunction "VDD_4") (pintype "unspecified"))
    )
    (net (code "128") (name "unconnected-(CARD2-DAT1-Pad8)") (class "Default")
      (node (ref "CARD2") (pin "8") (pinfunction "DAT1_8") (pintype "input+no_connect"))
    )
    (net (code "129") (name "unconnected-(CARD2-DAT2-Pad1)") (class "Default")
      (node (ref "CARD2") (pin "1") (pinfunction "DAT2_1") (pintype "input+no_connect"))
    )
    (net (code "130") (name "unconnected-(CARD2-PadCD)") (class "Default")
      (node (ref "CARD2") (pin "CD") (pinfunction "CD_CD") (pintype "input+no_connect"))
    )
    (net (code "131") (name "unconnected-(HDMI1-CEC-Pad13)") (class "Default")
      (node (ref "HDMI1") (pin "13") (pinfunction "CEC_13") (pintype "input+no_connect"))
    )
    (net (code "132") (name "unconnected-(HDMI1-Hot_Plug_Detect-Pad19)") (class "Default")
      (node (ref "HDMI1") (pin "19") (pinfunction "Hot_Plug_Detect_19") (pintype "input+no_connect"))
    )
    (net (code "133") (name "unconnected-(HDMI1-Reserved(N.C.)-Pad14)") (class "Default")
      (node (ref "HDMI1") (pin "14") (pinfunction "Reserved(N.C.)_14") (pintype "input+no_connect"))
    )
    (net (code "134") (name "unconnected-(HDMI1-SCL-Pad15)") (class "Default")
      (node (ref "HDMI1") (pin "15") (pinfunction "SCL_15") (pintype "input+no_connect"))
    )
    (net (code "135") (name "unconnected-(HDMI1-SDA-Pad16)") (class "Default")
      (node (ref "HDMI1") (pin "16") (pinfunction "SDA_16") (pintype "input+no_connect"))
    )
    (net (code "136") (name "unconnected-(U7-CTS#-Pad9)") (class "Default")
      (node (ref "U7") (pin "9") (pinfunction "CTS#_9") (pintype "input+no_connect"))
    )
    (net (code "137") (name "unconnected-(U7-DCD#-Pad12)") (class "Default")
      (node (ref "U7") (pin "12") (pinfunction "DCD#_12") (pintype "input+no_connect"))
    )
    (net (code "138") (name "unconnected-(U7-DSR#-Pad10)") (class "Default")
      (node (ref "U7") (pin "10") (pinfunction "DSR#_10") (pintype "input+no_connect"))
    )
    (net (code "139") (name "unconnected-(U7-DTR#-Pad13)") (class "Default")
      (node (ref "U7") (pin "13") (pinfunction "DTR#_13") (pintype "input+no_connect"))
    )
    (net (code "140") (name "unconnected-(U7-NC.-Pad7)") (class "Default")
      (node (ref "U7") (pin "7") (pinfunction "NC._7") (pintype "input+no_connect"))
    )
    (net (code "141") (name "unconnected-(U7-OUT#-Pad8)") (class "Default")
      (node (ref "U7") (pin "8") (pinfunction "OUT#_8") (pintype "input+no_connect"))
    )
    (net (code "142") (name "unconnected-(U7-R232-Pad15)") (class "Default")
      (node (ref "U7") (pin "15") (pinfunction "R232_15") (pintype "input+no_connect"))
    )
    (net (code "143") (name "unconnected-(U7-RI#-Pad11)") (class "Default")
      (node (ref "U7") (pin "11") (pinfunction "RI#_11") (pintype "input+no_connect"))
    )
    (net (code "144") (name "unconnected-(U7-RTS#-Pad14)") (class "Default")
      (node (ref "U7") (pin "14") (pinfunction "RTS#_14") (pintype "input+no_connect"))
    )
    (net (code "145") (name "unconnected-(U28-VREG_LX-Pad63)") (class "Default")
      (node (ref "U28") (pin "63") (pinfunction "VREG_LX_63") (pintype "unspecified+no_connect"))
    )
    (net (code "146") (name "unconnected-(U28-XOUT-Pad31)") (class "Default")
      (node (ref "U28") (pin "31") (pinfunction "XOUT_31") (pintype "unspecified+no_connect"))
    )
    (net (code "147") (name "unconnected-(U35-LED3{slash}SCL-Pad14)") (class "Default")
      (node (ref "U35") (pin "14") (pinfunction "LED3/SCL_14") (pintype "unspecified+no_connect"))
    )
    (net (code "148") (name "unconnected-(U35-NC-Pad18)") (class "Default")
      (node (ref "U35") (pin "18") (pinfunction "NC_18") (pintype "unspecified+no_connect"))
    )
    (net (code "149") (name "unconnected-(U35-NC-Pad27)") (class "Default")
      (node (ref "U35") (pin "27") (pinfunction "NC_27") (pintype "unspecified+no_connect"))
    )
    (net (code "150") (name "unconnected-(U35-PSELF-Pad19)") (class "Default")
      (node (ref "U35") (pin "19") (pinfunction "PSELF_19") (pintype "unspecified+no_connect"))
    )
    (net (code "151") (name "unconnected-(U36-GPIO1-Pad18)") (class "Default")
      (node (ref "U36") (pin "18") (pinfunction "GPIO1_18") (pintype "unspecified+no_connect"))
    )
    (net (code "152") (name "unconnected-(U36-GPIO2-Pad17)") (class "Default")
      (node (ref "U36") (pin "17") (pinfunction "GPIO2_17") (pintype "unspecified+no_connect"))
    )
    (net (code "153") (name "unconnected-(U36-nc-Pad2)") (class "Default")
      (node (ref "U36") (pin "2") (pinfunction "nc_2") (pintype "unspecified+no_connect"))
    )
    (net (code "154") (name "unconnected-(U36-nc-Pad19)") (class "Default")
      (node (ref "U36") (pin "19") (pinfunction "nc_19") (pintype "unspecified+no_connect"))
    )
    (net (code "155") (name "unconnected-(U36-nc-Pad20)") (class "Default")
      (node (ref "U36") (pin "20") (pinfunction "nc_20") (pintype "unspecified+no_connect"))
    )
    (net (code "156") (name "unconnected-(U37-NC-Pad4)") (class "Default")
      (node (ref "U37") (pin "4") (pinfunction "NC_4") (pintype "unspecified+no_connect"))
    )
    (net (code "157") (name "unconnected-(USB2-SUB1-PadA8)") (class "Default")
      (node (ref "USB2") (pin "A8") (pinfunction "SUB1_A8") (pintype "input+no_connect"))
    )
    (net (code "158") (name "unconnected-(USB2-SUB2-PadB8)") (class "Default")
      (node (ref "USB2") (pin "B8") (pinfunction "SUB2_B8") (pintype "input+no_connect"))
    )
    (net (code "159") (name "unconnected-(USB5-ID-Pad4)") (class "Default")
      (node (ref "USB5") (pin "4") (pinfunction "ID_4") (pintype "unspecified+no_connect"))
    )
  )
)
